# design.net
KiCad netlist of a schematic drawn in Altium Designer
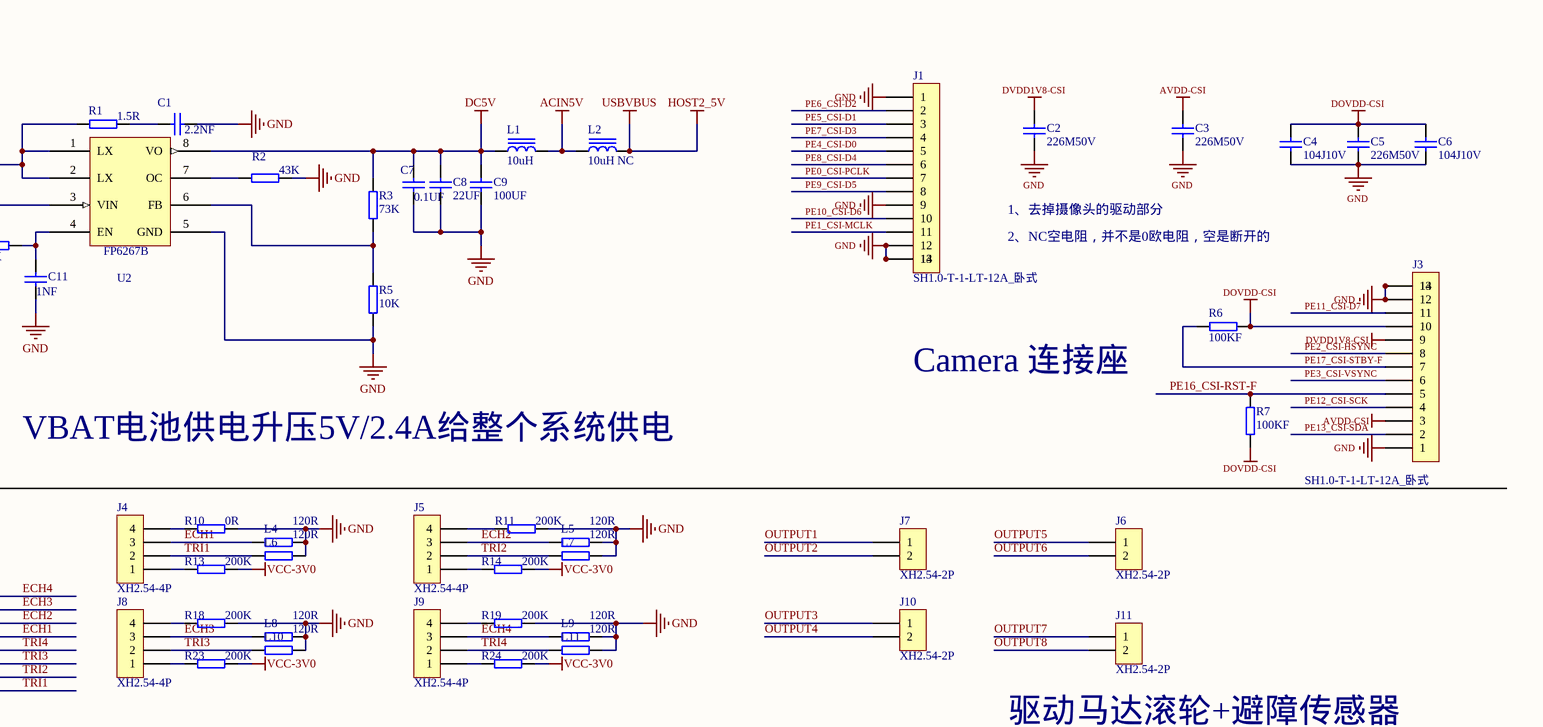
[diagram p0: 宠物机器人&导购机器人.SchDoc, top right]
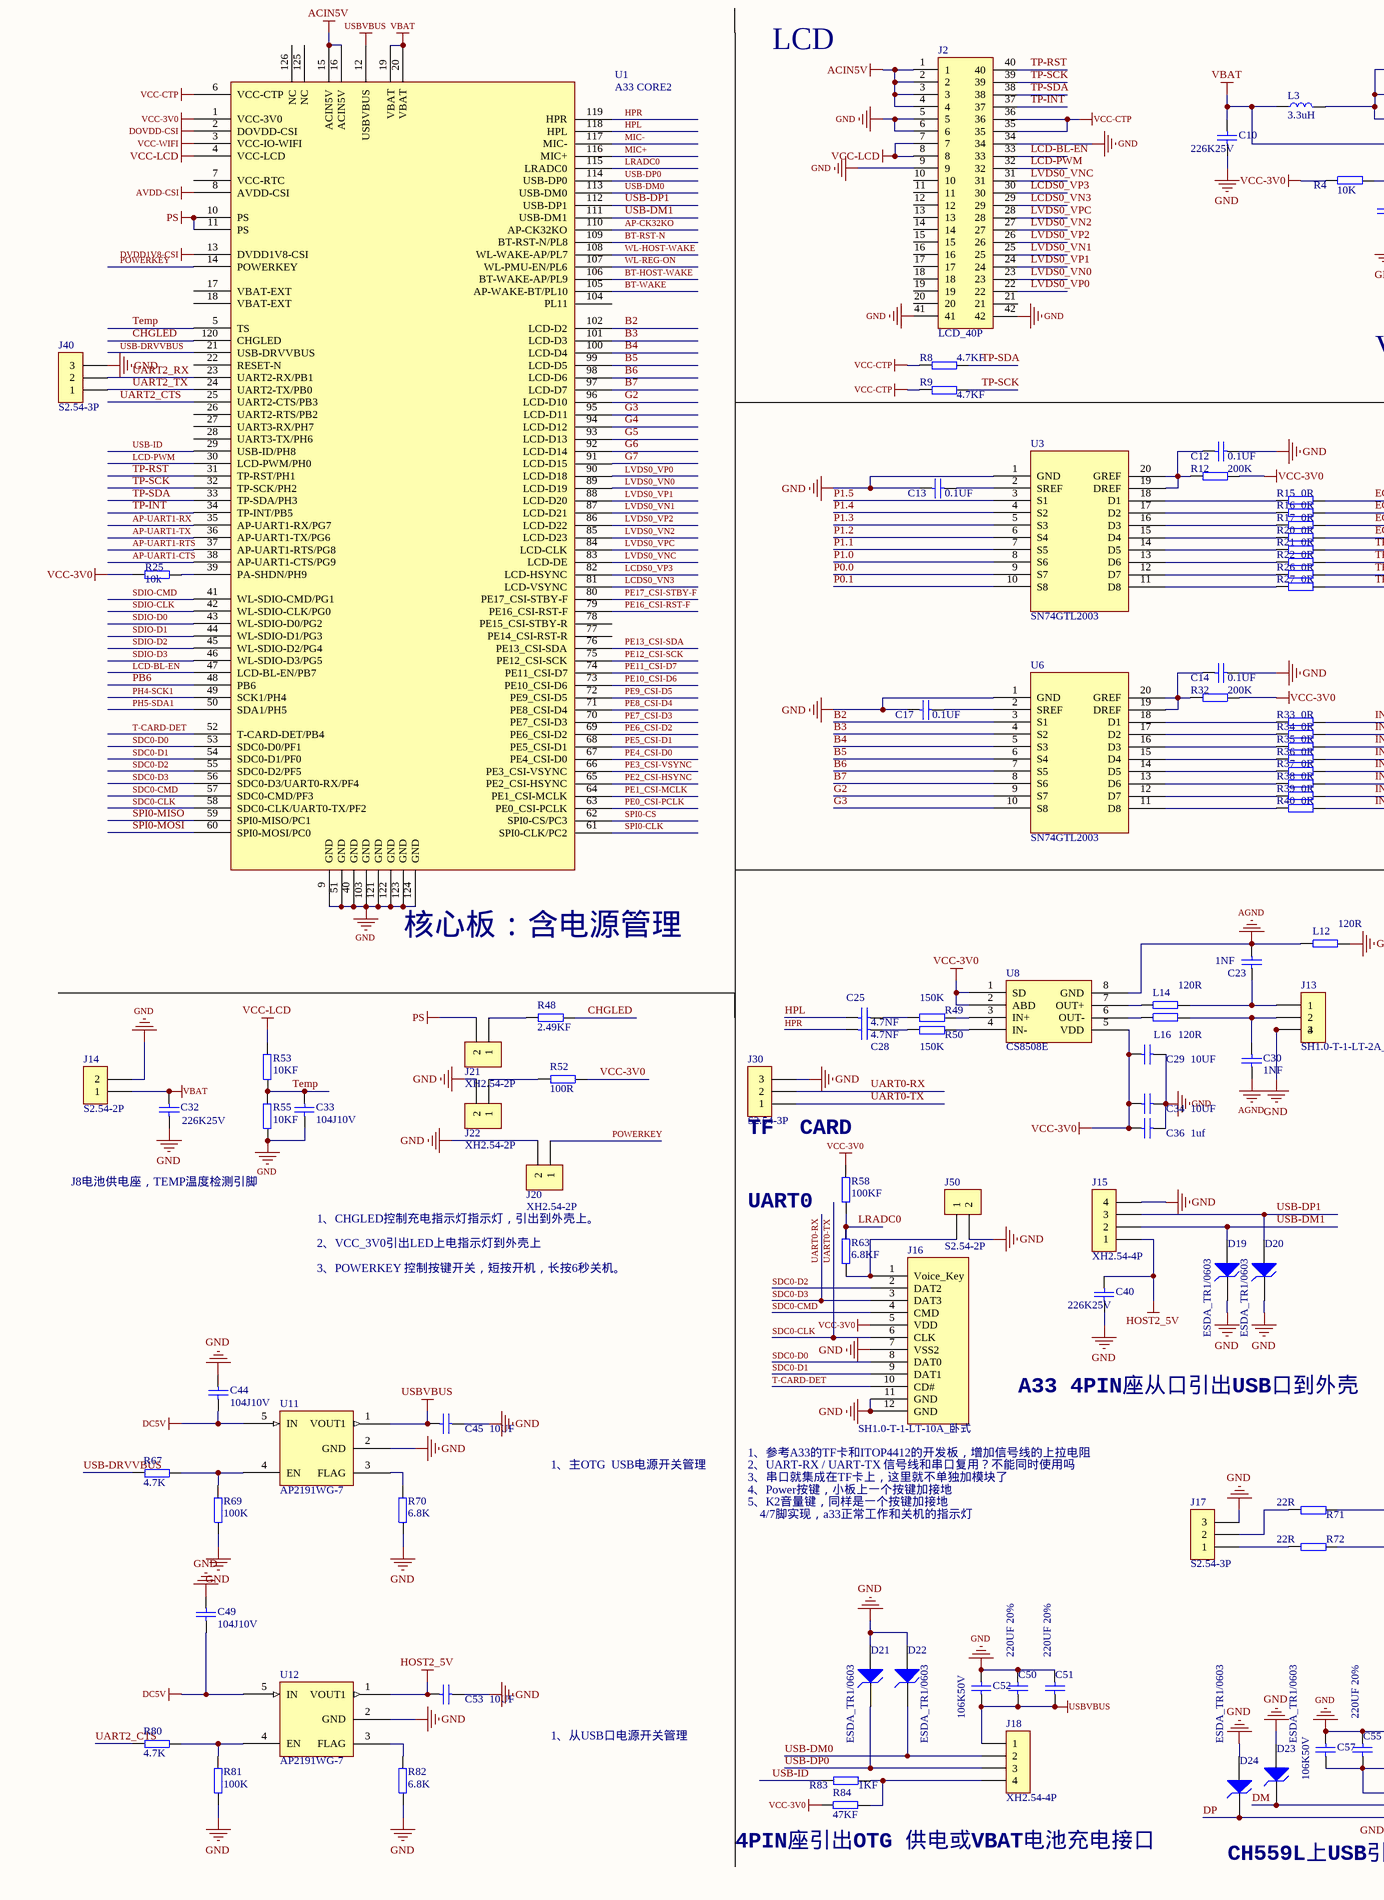
[diagram p1: 宠物机器人&导购机器人.SchDoc, bottom left]
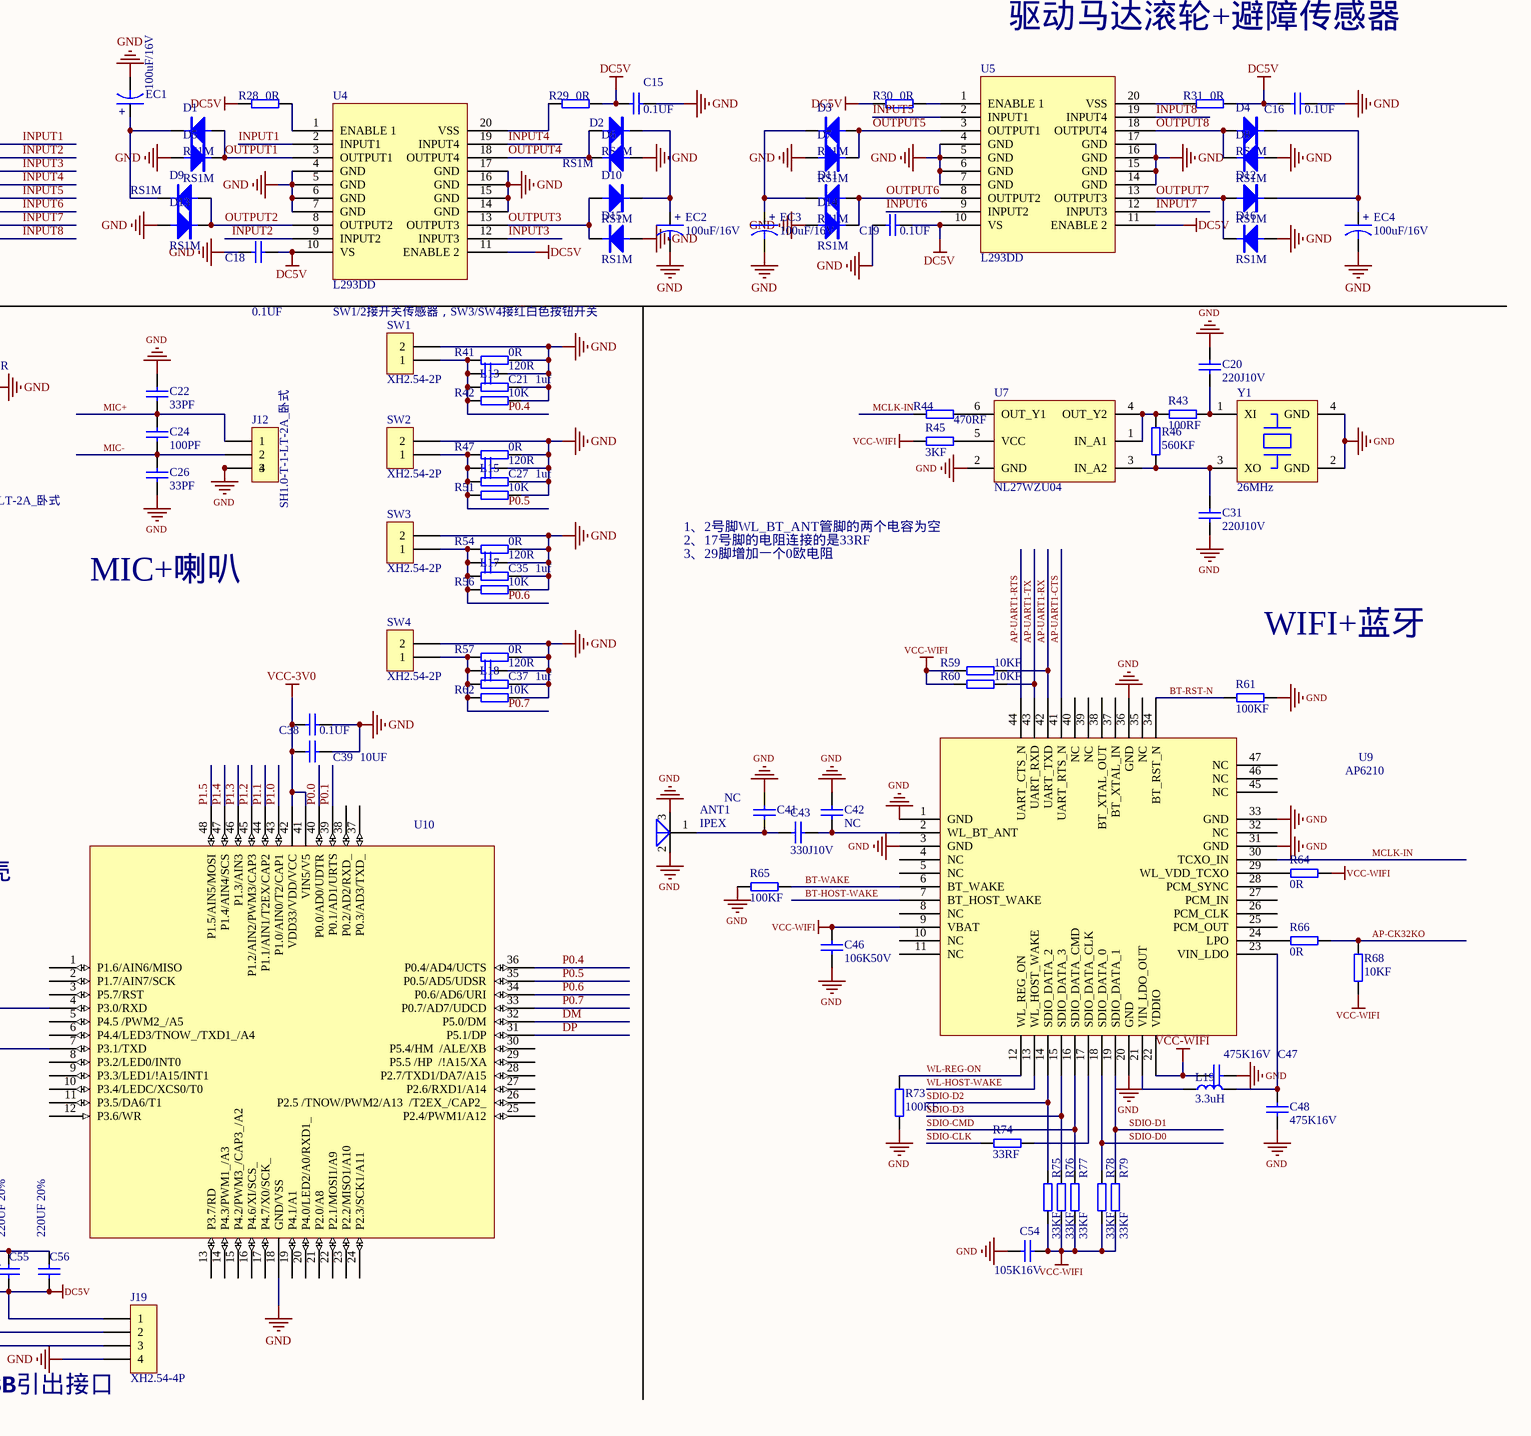
[diagram p2: 宠物机器人&导购机器人.SchDoc, bottom right]

(export (version "E")
  (design (tool "Eeschema 10.0.6"))
  (components
    (comp (ref "ANT1")
      (value "IPEX")
      (footprint "J-IPEX")
      (description "天线接口IPEX")
      (libsource (lib "Connector") (part "J-IPEX"))
    )
    (comp (ref "C1")
      (value "2.2NF")
      (footprint "C0603")
      (description "贴片电容-陶瓷")
      (libsource (lib "Capacitor") (part "C0603X7R-330J25V"))
    )
    (comp (ref "C2")
      (value "226M50V")
      (footprint "C0805")
      (description "贴片电容-陶瓷")
      (libsource (lib "Capacitor") (part "C0805Y5V-226M50V"))
    )
    (comp (ref "C3")
      (value "226M50V")
      (footprint "C0805")
      (description "贴片电容-陶瓷")
      (libsource (lib "Capacitor") (part "C0805Y5V-226M50V"))
    )
    (comp (ref "C4")
      (value "104J10V")
      (footprint "C0402")
      (description "贴片电容-陶瓷")
      (libsource (lib "Capacitor") (part "C0402X7R-104J10V"))
    )
    (comp (ref "C5")
      (value "226M50V")
      (footprint "C0805")
      (description "贴片电容-陶瓷")
      (libsource (lib "Capacitor") (part "C0805Y5V-226M50V"))
    )
    (comp (ref "C6")
      (value "104J10V")
      (footprint "C0402")
      (description "贴片电容-陶瓷")
      (libsource (lib "Capacitor") (part "C0402X7R-104J10V"))
    )
    (comp (ref "C7")
      (value "0.1UF")
      (footprint "C0402")
      (description "贴片电容-陶瓷")
      (libsource (lib "AIWAC-bolsterV01") (part "C0402X7R-101J10V"))
    )
    (comp (ref "C8")
      (value "22UF")
      (footprint "C0603")
      (description "贴片电容-陶瓷")
      (libsource (lib "Capacitor") (part "C0603X7R-330J25V"))
    )
    (comp (ref "C9")
      (value "100UF")
      (footprint "CD3X5.3SMD")
      (description "贴片电容-陶瓷")
      (libsource (lib "Capacitor") (part "C0603X7R-330J25V"))
    )
    (comp (ref "C10")
      (value "226K25V")
      (footprint "C0805")
      (description "贴片电容-陶瓷")
      (libsource (lib "Capacitor") (part "C0805X7R-226K25V"))
    )
    (comp (ref "C11")
      (value "1NF")
      (footprint "C0402")
      (description "贴片电容-陶瓷")
      (libsource (lib "AIWAC-bolsterV01") (part "C0402X7R-101J10V"))
    )
    (comp (ref "C12")
      (value "0.1UF")
      (footprint "C0603")
      (description "贴片电容-陶瓷")
      (libsource (lib "Capacitor") (part "C0603X7R-330J25V"))
    )
    (comp (ref "C13")
      (value "0.1UF")
      (footprint "C0603")
      (description "贴片电容-陶瓷")
      (libsource (lib "Capacitor") (part "C0603X7R-330J25V"))
    )
    (comp (ref "C14")
      (value "0.1UF")
      (footprint "C0603")
      (description "贴片电容-陶瓷")
      (libsource (lib "Capacitor") (part "C0603X7R-330J25V"))
    )
    (comp (ref "C15")
      (value "0.1UF")
      (footprint "C0603")
      (description "贴片电容-陶瓷")
      (libsource (lib "Capacitor") (part "C0603X7R-330J25V"))
    )
    (comp (ref "C16")
      (value "0.1UF")
      (footprint "C0603")
      (description "贴片电容-陶瓷")
      (libsource (lib "Capacitor") (part "C0603X7R-330J25V"))
    )
    (comp (ref "C17")
      (value "0.1UF")
      (footprint "C0603")
      (description "贴片电容-陶瓷")
      (libsource (lib "Capacitor") (part "C0603X7R-330J25V"))
    )
    (comp (ref "C18")
      (value "0.1UF")
      (footprint "C0603")
      (description "贴片电容-陶瓷")
      (libsource (lib "Capacitor") (part "C0603X7R-330J25V"))
    )
    (comp (ref "C19")
      (value "0.1UF")
      (footprint "C0603")
      (description "贴片电容-陶瓷")
      (libsource (lib "Capacitor") (part "C0603X7R-330J25V"))
    )
    (comp (ref "C20")
      (value "220J10V")
      (footprint "C0402")
      (description "贴片电容-陶瓷")
      (libsource (lib "Capacitor") (part "C0402X7R-220J10V"))
    )
    (comp (ref "C21")
      (value "1uf")
      (footprint "C0603")
      (description "贴片电容-陶瓷")
      (libsource (lib "Capacitor") (part "C0603X7R-330J25V"))
    )
    (comp (ref "C22")
      (value "33PF")
      (footprint "C0402")
      (description "贴片电容-陶瓷")
      (libsource (lib "Capacitor") (part "C0402X7R-104J10V"))
    )
    (comp (ref "C23")
      (value "1NF")
      (footprint "C0402")
      (description "贴片电容-陶瓷")
      (libsource (lib "Capacitor") (part "C0402X7R-220J10V"))
    )
    (comp (ref "C24")
      (value "100PF")
      (footprint "C0402")
      (description "贴片电容-陶瓷")
      (libsource (lib "Capacitor") (part "C0402X7R-104J10V"))
    )
    (comp (ref "C25")
      (value "4.7NF")
      (footprint "C0603")
      (description "贴片电容-陶瓷")
      (libsource (lib "Capacitor") (part "C0603X7R-330J25V"))
    )
    (comp (ref "C26")
      (value "33PF")
      (footprint "C0402")
      (description "贴片电容-陶瓷")
      (libsource (lib "Capacitor") (part "C0402X7R-104J10V"))
    )
    (comp (ref "C27")
      (value "1uf")
      (footprint "C0603")
      (description "贴片电容-陶瓷")
      (libsource (lib "Capacitor") (part "C0603X7R-330J25V"))
    )
    (comp (ref "C28")
      (value "4.7NF")
      (footprint "C0603")
      (description "贴片电容-陶瓷")
      (libsource (lib "Capacitor") (part "C0603X7R-330J25V"))
    )
    (comp (ref "C29")
      (value "10UF")
      (footprint "C0603")
      (description "贴片电容-陶瓷")
      (libsource (lib "Capacitor") (part "C0603X7R-330J25V"))
    )
    (comp (ref "C30")
      (value "1NF")
      (footprint "C0402")
      (description "贴片电容-陶瓷")
      (libsource (lib "Capacitor") (part "C0402X7R-220J10V"))
    )
    (comp (ref "C31")
      (value "220J10V")
      (footprint "C0402")
      (description "贴片电容-陶瓷")
      (libsource (lib "Capacitor") (part "C0402X7R-220J10V"))
    )
    (comp (ref "C32")
      (value "226K25V")
      (footprint "C0805")
      (description "贴片电容-陶瓷")
      (libsource (lib "Capacitor") (part "C0805X7R-226K25V"))
    )
    (comp (ref "C33")
      (value "104J10V")
      (footprint "C0402")
      (description "贴片电容-陶瓷")
      (libsource (lib "Capacitor") (part "C0402X7R-104J10V"))
    )
    (comp (ref "C34")
      (value "10UF")
      (footprint "C0603")
      (description "贴片电容-陶瓷")
      (libsource (lib "Capacitor") (part "C0603X7R-330J25V"))
    )
    (comp (ref "C35")
      (value "1uf")
      (footprint "C0603")
      (description "贴片电容-陶瓷")
      (libsource (lib "Capacitor") (part "C0603X7R-330J25V"))
    )
    (comp (ref "C36")
      (value "1uf")
      (footprint "C0603")
      (description "贴片电容-陶瓷")
      (libsource (lib "Capacitor") (part "C0603X7R-330J25V"))
    )
    (comp (ref "C37")
      (value "1uf")
      (footprint "C0603")
      (description "贴片电容-陶瓷")
      (libsource (lib "Capacitor") (part "C0603X7R-330J25V"))
    )
    (comp (ref "C38")
      (value "0.1UF")
      (footprint "C0603")
      (description "贴片电容-陶瓷")
      (libsource (lib "Capacitor") (part "C0603X7R-330J25V"))
    )
    (comp (ref "C39")
      (value "10UF")
      (footprint "C0603")
      (description "贴片电容-陶瓷")
      (libsource (lib "Capacitor") (part "C0603X7R-330J25V"))
    )
    (comp (ref "C40")
      (value "226K25V")
      (footprint "C0805")
      (description "贴片电容-陶瓷")
      (libsource (lib "Capacitor") (part "C0805X7R-226K25V"))
    )
    (comp (ref "C41")
      (value "NC")
      (footprint "C0402")
      (description "贴片电容-陶瓷")
      (libsource (lib "Capacitor") (part "C0402X7R-220J10V"))
    )
    (comp (ref "C42")
      (value "NC")
      (footprint "C0402")
      (description "贴片电容-陶瓷")
      (libsource (lib "Capacitor") (part "C0402X7R-220J10V"))
    )
    (comp (ref "C43")
      (value "330J10V")
      (footprint "C0402")
      (description "贴片电容-陶瓷")
      (libsource (lib "Capacitor") (part "C0402X7R-330J10V"))
    )
    (comp (ref "C44")
      (value "104J10V")
      (footprint "C0402")
      (description "贴片电容-陶瓷")
      (libsource (lib "Capacitor") (part "C0402X7R-104J10V"))
    )
    (comp (ref "C45")
      (value "10UF")
      (footprint "C0603")
      (description "贴片电容-陶瓷")
      (libsource (lib "Capacitor") (part "C0603X7R-330J25V"))
    )
    (comp (ref "C46")
      (value "106K50V")
      (footprint "C0603")
      (description "贴片电容-陶瓷")
      (libsource (lib "Capacitor") (part "C0603X7R-106K50V"))
    )
    (comp (ref "C47")
      (value "475K16V")
      (footprint "C0603")
      (description "贴片电容-陶瓷")
      (libsource (lib "Capacitor") (part "C0603X7R-475K16V"))
    )
    (comp (ref "C48")
      (value "475K16V")
      (footprint "C0603")
      (description "贴片电容-陶瓷")
      (libsource (lib "Capacitor") (part "C0603X7R-475K16V"))
    )
    (comp (ref "C49")
      (value "104J10V")
      (footprint "C0402")
      (description "贴片电容-陶瓷")
      (libsource (lib "Capacitor") (part "C0402X7R-104J10V"))
    )
    (comp (ref "C50")
      (value "220UF 20%")
      (footprint "C1206")
      (description "C 1206钽电容 --220UF 10V 3216 A型 有极性电容 3.2mm X 1.6mm")
      (libsource (lib "Capacitor") (part "C1206-A型 极性电容"))
    )
    (comp (ref "C51")
      (value "220UF 20%")
      (footprint "C1206")
      (description "C 1206钽电容 --220UF 10V 3216 A型 有极性电容 3.2mm X 1.6mm")
      (libsource (lib "Capacitor") (part "C1206-A型 极性电容"))
    )
    (comp (ref "C52")
      (value "106K50V")
      (footprint "C0603")
      (description "贴片电容-陶瓷")
      (libsource (lib "Capacitor") (part "C0603X7R-106K50V"))
    )
    (comp (ref "C53")
      (value "10UF")
      (footprint "C0603")
      (description "贴片电容-陶瓷")
      (libsource (lib "Capacitor") (part "C0603X7R-330J25V"))
    )
    (comp (ref "C54")
      (value "105K16V")
      (footprint "C0603")
      (description "贴片电容-陶瓷")
      (libsource (lib "Capacitor") (part "C0603X7R-105K16V"))
    )
    (comp (ref "C55")
      (value "220UF 20%")
      (footprint "C1206")
      (description "C 1206钽电容 --220UF 10V 3216 A型 有极性电容 3.2mm X 1.6mm")
      (libsource (lib "Capacitor") (part "C1206-A型 极性电容"))
    )
    (comp (ref "C56")
      (value "220UF 20%")
      (footprint "C1206")
      (description "C 1206钽电容 --220UF 10V 3216 A型 有极性电容 3.2mm X 1.6mm")
      (libsource (lib "Capacitor") (part "C1206-A型 极性电容"))
    )
    (comp (ref "C57")
      (value "106K50V")
      (footprint "C0603")
      (description "贴片电容-陶瓷")
      (libsource (lib "Capacitor") (part "C0603X7R-106K50V"))
    )
    (comp (ref "D1")
      (value "RS1M")
      (footprint "D-SMA/DO-214AC")
      (description "贴片二极管-快恢复")
      (libsource (lib "Sheye-Diode") (part "DF-RS1M-1A1000V"))
    )
    (comp (ref "D2")
      (value "RS1M")
      (footprint "D-SMA/DO-214AC")
      (description "贴片二极管-快恢复")
      (libsource (lib "Sheye-Diode") (part "DF-RS1M-1A1000V"))
    )
    (comp (ref "D3")
      (value "RS1M")
      (footprint "D-SMA/DO-214AC")
      (description "贴片二极管-快恢复")
      (libsource (lib "Sheye-Diode") (part "DF-RS1M-1A1000V"))
    )
    (comp (ref "D4")
      (value "RS1M")
      (footprint "D-SMA/DO-214AC")
      (description "贴片二极管-快恢复")
      (libsource (lib "Sheye-Diode") (part "DF-RS1M-1A1000V"))
    )
    (comp (ref "D5")
      (value "RS1M")
      (footprint "D-SMA/DO-214AC")
      (description "贴片二极管-快恢复")
      (libsource (lib "Sheye-Diode") (part "DF-RS1M-1A1000V"))
    )
    (comp (ref "D6")
      (value "RS1M")
      (footprint "D-SMA/DO-214AC")
      (description "贴片二极管-快恢复")
      (libsource (lib "Sheye-Diode") (part "DF-RS1M-1A1000V"))
    )
    (comp (ref "D7")
      (value "RS1M")
      (footprint "D-SMA/DO-214AC")
      (description "贴片二极管-快恢复")
      (libsource (lib "Sheye-Diode") (part "DF-RS1M-1A1000V"))
    )
    (comp (ref "D8")
      (value "RS1M")
      (footprint "D-SMA/DO-214AC")
      (description "贴片二极管-快恢复")
      (libsource (lib "Sheye-Diode") (part "DF-RS1M-1A1000V"))
    )
    (comp (ref "D9")
      (value "RS1M")
      (footprint "D-SMA/DO-214AC")
      (description "贴片二极管-快恢复")
      (libsource (lib "Sheye-Diode") (part "DF-RS1M-1A1000V"))
    )
    (comp (ref "D10")
      (value "RS1M")
      (footprint "D-SMA/DO-214AC")
      (description "贴片二极管-快恢复")
      (libsource (lib "Sheye-Diode") (part "DF-RS1M-1A1000V"))
    )
    (comp (ref "D11")
      (value "RS1M")
      (footprint "D-SMA/DO-214AC")
      (description "贴片二极管-快恢复")
      (libsource (lib "Sheye-Diode") (part "DF-RS1M-1A1000V"))
    )
    (comp (ref "D12")
      (value "RS1M")
      (footprint "D-SMA/DO-214AC")
      (description "贴片二极管-快恢复")
      (libsource (lib "Sheye-Diode") (part "DF-RS1M-1A1000V"))
    )
    (comp (ref "D13")
      (value "RS1M")
      (footprint "D-SMA/DO-214AC")
      (description "贴片二极管-快恢复")
      (libsource (lib "Sheye-Diode") (part "DF-RS1M-1A1000V"))
    )
    (comp (ref "D14")
      (value "RS1M")
      (footprint "D-SMA/DO-214AC")
      (description "贴片二极管-快恢复")
      (libsource (lib "Sheye-Diode") (part "DF-RS1M-1A1000V"))
    )
    (comp (ref "D15")
      (value "RS1M")
      (footprint "D-SMA/DO-214AC")
      (description "贴片二极管-快恢复")
      (libsource (lib "Sheye-Diode") (part "DF-RS1M-1A1000V"))
    )
    (comp (ref "D16")
      (value "RS1M")
      (footprint "D-SMA/DO-214AC")
      (description "贴片二极管-快恢复")
      (libsource (lib "Sheye-Diode") (part "DF-RS1M-1A1000V"))
    )
    (comp (ref "D19")
      (value "ESDA_TR1/0603")
      (footprint "HS_0603D")
      (description "Zener Diode")
      (fields (field (name "PUBLISHER") "*"))
      (libsource (lib "1_1") (part "D Zener"))
    )
    (comp (ref "D20")
      (value "ESDA_TR1/0603")
      (footprint "HS_0603D")
      (description "Zener Diode")
      (fields (field (name "PUBLISHER") "*"))
      (libsource (lib "1_1") (part "D Zener"))
    )
    (comp (ref "D21")
      (value "ESDA_TR1/0603")
      (footprint "HS_0603D")
      (description "Zener Diode")
      (fields (field (name "PUBLISHER") "*"))
      (libsource (lib "1_1") (part "D Zener"))
    )
    (comp (ref "D22")
      (value "ESDA_TR1/0603")
      (footprint "HS_0603D")
      (description "Zener Diode")
      (fields (field (name "PUBLISHER") "*"))
      (libsource (lib "1_1") (part "D Zener"))
    )
    (comp (ref "D23")
      (value "ESDA_TR1/0603")
      (footprint "HS_0603D")
      (description "Zener Diode")
      (fields (field (name "PUBLISHER") "*"))
      (libsource (lib "1_1") (part "D Zener"))
    )
    (comp (ref "D24")
      (value "ESDA_TR1/0603")
      (footprint "HS_0603D")
      (description "Zener Diode")
      (fields (field (name "PUBLISHER") "*"))
      (libsource (lib "1_1") (part "D Zener"))
    )
    (comp (ref "EC1")
      (value "100uF/16V")
      (footprint "CD6.3x8SMD")
      (description "贴片铝电解电容")
      (libsource (lib "Sheye-Capacitor") (part "CES-100uF/16V"))
    )
    (comp (ref "EC2")
      (value "100uF/16V")
      (footprint "CD6.3x8SMD")
      (description "贴片铝电解电容")
      (libsource (lib "Sheye-Capacitor") (part "CES-100uF/16V"))
    )
    (comp (ref "EC3")
      (value "100uF/16V")
      (footprint "CD6.3x8SMD")
      (description "贴片铝电解电容")
      (libsource (lib "Sheye-Capacitor") (part "CES-100uF/16V"))
    )
    (comp (ref "EC4")
      (value "100uF/16V")
      (footprint "CD6.3x8SMD")
      (description "贴片铝电解电容")
      (libsource (lib "Sheye-Capacitor") (part "CES-100uF/16V"))
    )
    (comp (ref "J1")
      (value "SH1.0-T-1-LT-12A_卧式")
      (footprint "J-SH1.0-T-1-LT-12A_立式")
      (libsource (lib "") (part "SH1.0-T-1-LT-12A_卧式_1"))
    )
    (comp (ref "J2") (value "LCD_40P") (footprint "LCD P40") (libsource (lib "Connector") (part "LCD_40P")))
    (comp (ref "J3")
      (value "SH1.0-T-1-LT-12A_卧式")
      (footprint "J-SH1.0-T-1-LT-12A_立式")
      (libsource (lib "Connector") (part "SH1.0-T-1-LT-12A_卧式"))
    )
    (comp (ref "J4")
      (value "XH2.54-4P")
      (footprint "XH2.54-4P")
      (description "接插件-2.54")
      (libsource (lib "AIWAC-bolsterV01") (part "J-XH2.54-4P"))
    )
    (comp (ref "J5")
      (value "XH2.54-4P")
      (footprint "XH2.54-4P")
      (description "接插件-2.54")
      (libsource (lib "AIWAC-bolsterV01") (part "J-XH2.54-4P"))
    )
    (comp (ref "J6")
      (value "XH2.54-2P")
      (footprint "XH2.54-2P")
      (description "接插件-2.54")
      (libsource (lib "AIWAC-bolsterV01") (part "J-XH2.54-2P"))
    )
    (comp (ref "J7")
      (value "XH2.54-2P")
      (footprint "XH2.54-2P")
      (description "接插件-2.54")
      (libsource (lib "AIWAC-bolsterV01") (part "J-XH2.54-2P"))
    )
    (comp (ref "J8")
      (value "XH2.54-4P")
      (footprint "XH2.54-4P")
      (description "接插件-2.54")
      (libsource (lib "AIWAC-bolsterV01") (part "J-XH2.54-4P"))
    )
    (comp (ref "J9")
      (value "XH2.54-4P")
      (footprint "XH2.54-4P")
      (description "接插件-2.54")
      (libsource (lib "AIWAC-bolsterV01") (part "J-XH2.54-4P"))
    )
    (comp (ref "J10")
      (value "XH2.54-2P")
      (footprint "XH2.54-2P")
      (description "接插件-2.54")
      (libsource (lib "AIWAC-bolsterV01") (part "J-XH2.54-2P"))
    )
    (comp (ref "J11")
      (value "XH2.54-2P")
      (footprint "XH2.54-2P")
      (description "接插件-2.54")
      (libsource (lib "AIWAC-bolsterV01") (part "J-XH2.54-2P"))
    )
    (comp (ref "J12")
      (value "SH1.0-T-1-LT-2A_卧式")
      (footprint "J-SH2.0-T-1-LT-2A_立式")
      (libsource (lib "Connector") (part "SH1.0-T-1-LT-2A_卧式"))
    )
    (comp (ref "J13")
      (value "SH1.0-T-1-LT-2A_卧式")
      (footprint "J-SH2.0-T-1-LT-2A_立式")
      (libsource (lib "Connector") (part "SH1.0-T-1-LT-2A_卧式"))
    )
    (comp (ref "J14")
      (value "S2.54-2P")
      (footprint "S2.54-2P")
      (description "单排排针-直针")
      (libsource (lib "Sheye-Connector") (part "J-S2.54-2P"))
    )
    (comp (ref "J15")
      (value "XH2.54-4P")
      (footprint "XH2.54-4P")
      (description "接插件-2.54")
      (libsource (lib "Sheye-Connector") (part "J-XH2.54-4P"))
    )
    (comp (ref "J16")
      (value "SH1.0-T-1-LT-10A_卧式")
      (footprint "J-SH1.0-T-1-LT-10A_立式")
      (libsource (lib "Connector") (part "SH1.0-T-1-LT-10A_卧式"))
    )
    (comp (ref "J17")
      (value "S2.54-3P")
      (footprint "S2.54-3P")
      (description "单排排针-直针")
      (libsource (lib "Sheye-Connector") (part "J-S2.54-3P"))
    )
    (comp (ref "J18")
      (value "XH2.54-4P")
      (footprint "XH2.54-4P")
      (description "接插件-2.54")
      (libsource (lib "") (part "J-XH2.54-4P_1"))
    )
    (comp (ref "J19")
      (value "XH2.54-4P")
      (footprint "XH2.54-4P")
      (description "接插件-2.54")
      (libsource (lib "") (part "J-XH2.54-4P_1"))
    )
    (comp (ref "J20")
      (value "XH2.54-2P")
      (footprint "XH2.54-2P")
      (description "接插件-2.54")
      (libsource (lib "") (part "J-XH2.54-2P_1"))
    )
    (comp (ref "J21")
      (value "XH2.54-2P")
      (footprint "XH2.54-2P")
      (description "接插件-2.54")
      (libsource (lib "") (part "J-XH2.54-2P_1"))
    )
    (comp (ref "J22")
      (value "XH2.54-2P")
      (footprint "XH2.54-2P")
      (description "接插件-2.54")
      (libsource (lib "") (part "J-XH2.54-2P_1"))
    )
    (comp (ref "J30")
      (value "S2.54-3P")
      (footprint "S2.54-3P")
      (description "单排排针-直针")
      (libsource (lib "PCB_Project") (part "J-S2.54-3P"))
    )
    (comp (ref "J40")
      (value "S2.54-3P")
      (footprint "S2.54-3P")
      (description "单排排针-直针")
      (libsource (lib "PCB_Project") (part "J-S2.54-3P"))
    )
    (comp (ref "J50")
      (value "S2.54-2P")
      (footprint "S2.54-2P")
      (description "单排排针-直针")
      (libsource (lib "PCB_Project") (part "J-S2.54-2P"))
    )
    (comp (ref "L1")
      (value "10uH")
      (footprint "C0603")
      (description "插件电感-工形")
      (libsource (lib "AIWAC-bolsterV01") (part "LI-0608-10uH1A"))
    )
    (comp (ref "L2")
      (value "10uH NC")
      (footprint "C0603")
      (description "插件电感-工形")
      (libsource (lib "AIWAC-bolsterV01") (part "LI-0608-10uH1A"))
    )
    (comp (ref "L3")
      (value "3.3uH")
      (footprint "LSMD3521")
      (description "贴片电感-屏蔽")
      (libsource (lib "AIWAC-bolsterV01") (part "3.3uH"))
    )
    (comp (ref "L4")
      (value "120R")
      (footprint "R0603")
      (description "贴片电阻-通用")
      (libsource (lib "Resistor") (part "R0603-47KF"))
    )
    (comp (ref "L5")
      (value "120R")
      (footprint "R0603")
      (description "贴片电阻-通用")
      (libsource (lib "Resistor") (part "R0603-47KF"))
    )
    (comp (ref "L6")
      (value "120R")
      (footprint "R0603")
      (description "贴片电阻-通用")
      (libsource (lib "Resistor") (part "R0603-47KF"))
    )
    (comp (ref "L7")
      (value "120R")
      (footprint "R0603")
      (description "贴片电阻-通用")
      (libsource (lib "Resistor") (part "R0603-47KF"))
    )
    (comp (ref "L8")
      (value "120R")
      (footprint "R0603")
      (description "贴片电阻-通用")
      (libsource (lib "Resistor") (part "R0603-47KF"))
    )
    (comp (ref "L9")
      (value "120R")
      (footprint "R0603")
      (description "贴片电阻-通用")
      (libsource (lib "Resistor") (part "R0603-47KF"))
    )
    (comp (ref "L10")
      (value "120R")
      (footprint "R0603")
      (description "贴片电阻-通用")
      (libsource (lib "Resistor") (part "R0603-47KF"))
    )
    (comp (ref "L11")
      (value "120R")
      (footprint "R0603")
      (description "贴片电阻-通用")
      (libsource (lib "Resistor") (part "R0603-47KF"))
    )
    (comp (ref "L12")
      (value "120R")
      (footprint "R0603")
      (description "贴片电阻-通用")
      (libsource (lib "Resistor") (part "R0603-47KF"))
    )
    (comp (ref "L13")
      (value "120R")
      (footprint "R0603")
      (description "贴片电阻-通用")
      (libsource (lib "Resistor") (part "R0603-47KF"))
    )
    (comp (ref "L14")
      (value "120R")
      (footprint "R0603")
      (description "贴片电阻-通用")
      (libsource (lib "Resistor") (part "R0603-47KF"))
    )
    (comp (ref "L15")
      (value "120R")
      (footprint "R0603")
      (description "贴片电阻-通用")
      (libsource (lib "Resistor") (part "R0603-47KF"))
    )
    (comp (ref "L16")
      (value "120R")
      (footprint "R0603")
      (description "贴片电阻-通用")
      (libsource (lib "Resistor") (part "R0603-47KF"))
    )
    (comp (ref "L17")
      (value "120R")
      (footprint "R0603")
      (description "贴片电阻-通用")
      (libsource (lib "Resistor") (part "R0603-47KF"))
    )
    (comp (ref "L18")
      (value "120R")
      (footprint "R0603")
      (description "贴片电阻-通用")
      (libsource (lib "Resistor") (part "R0603-47KF"))
    )
    (comp (ref "L19")
      (value "3.3uH")
      (footprint "L0805")
      (description "贴片电感-层叠")
      (libsource (lib "magnetic") (part "L-0805-3.3uH"))
    )
    (comp (ref "R1")
      (value "1.5R")
      (footprint "R0603")
      (description "贴片电阻-通用")
      (libsource (lib "Resistor") (part "R0603-2KF"))
    )
    (comp (ref "R2")
      (value "43K")
      (footprint "R0603")
      (description "贴片电阻-通用")
      (libsource (lib "Resistor") (part "R0603-2KF"))
    )
    (comp (ref "R3")
      (value "73K")
      (footprint "R0603")
      (description "贴片电阻-通用")
      (libsource (lib "Resistor") (part "R0603-2KF"))
    )
    (comp (ref "R4")
      (value "10K")
      (footprint "R0603")
      (description "贴片电阻-通用")
      (libsource (lib "Resistor") (part "R0603-2KF"))
    )
    (comp (ref "R5")
      (value "10K")
      (footprint "R0603")
      (description "贴片电阻-通用")
      (libsource (lib "Resistor") (part "R0603-2KF"))
    )
    (comp (ref "R6")
      (value "100KF")
      (footprint "R0603")
      (description "贴片电阻-通用")
      (libsource (lib "Resistor") (part "R0603-100KF"))
    )
    (comp (ref "R7")
      (value "100KF")
      (footprint "R0603")
      (description "贴片电阻-通用")
      (libsource (lib "Resistor") (part "R0603-100KF"))
    )
    (comp (ref "R8")
      (value "4.7KF")
      (footprint "R0402")
      (description "贴片电阻-通用")
      (libsource (lib "Resistor") (part "R0402-4.7KF"))
    )
    (comp (ref "R9")
      (value "4.7KF")
      (footprint "R0402")
      (description "贴片电阻-通用")
      (libsource (lib "Resistor") (part "R0402-4.7KF"))
    )
    (comp (ref "R10")
      (value "0R")
      (footprint "R0402")
      (description "贴片电阻-通用")
      (libsource (lib "Resistor") (part "R0402-4.7KF"))
    )
    (comp (ref "R11")
      (value "200K")
      (footprint "R0402")
      (description "贴片电阻-通用")
      (libsource (lib "Resistor") (part "R0402-4.7KF"))
    )
    (comp (ref "R12")
      (value "200K")
      (footprint "R0402")
      (description "贴片电阻-通用")
      (libsource (lib "Resistor") (part "R0402-4.7KF"))
    )
    (comp (ref "R13")
      (value "200K")
      (footprint "R0402")
      (description "贴片电阻-通用")
      (libsource (lib "Resistor") (part "R0402-4.7KF"))
    )
    (comp (ref "R14")
      (value "200K")
      (footprint "R0402")
      (description "贴片电阻-通用")
      (libsource (lib "Resistor") (part "R0402-4.7KF"))
    )
    (comp (ref "R15")
      (value "0R")
      (footprint "R0603")
      (description "贴片电阻-通用")
      (libsource (lib "Resistor") (part "R0603-2KF"))
    )
    (comp (ref "R16")
      (value "0R")
      (footprint "R0603")
      (description "贴片电阻-通用")
      (libsource (lib "Resistor") (part "R0603-2KF"))
    )
    (comp (ref "R17")
      (value "0R")
      (footprint "R0603")
      (description "贴片电阻-通用")
      (libsource (lib "Resistor") (part "R0603-2KF"))
    )
    (comp (ref "R18")
      (value "200K")
      (footprint "R0402")
      (description "贴片电阻-通用")
      (libsource (lib "Resistor") (part "R0402-4.7KF"))
    )
    (comp (ref "R19")
      (value "200K")
      (footprint "R0402")
      (description "贴片电阻-通用")
      (libsource (lib "Resistor") (part "R0402-4.7KF"))
    )
    (comp (ref "R20")
      (value "0R")
      (footprint "R0603")
      (description "贴片电阻-通用")
      (libsource (lib "Resistor") (part "R0603-2KF"))
    )
    (comp (ref "R21")
      (value "0R")
      (footprint "R0603")
      (description "贴片电阻-通用")
      (libsource (lib "Resistor") (part "R0603-2KF"))
    )
    (comp (ref "R22")
      (value "0R")
      (footprint "R0603")
      (description "贴片电阻-通用")
      (libsource (lib "Resistor") (part "R0603-2KF"))
    )
    (comp (ref "R23")
      (value "200K")
      (footprint "R0402")
      (description "贴片电阻-通用")
      (libsource (lib "Resistor") (part "R0402-4.7KF"))
    )
    (comp (ref "R24")
      (value "200K")
      (footprint "R0402")
      (description "贴片电阻-通用")
      (libsource (lib "Resistor") (part "R0402-4.7KF"))
    )
    (comp (ref "R25")
      (value "10k")
      (footprint "R0603")
      (description "贴片电阻-通用")
      (libsource (lib "Resistor") (part "R0603-10KF"))
    )
    (comp (ref "R26")
      (value "0R")
      (footprint "R0603")
      (description "贴片电阻-通用")
      (libsource (lib "Resistor") (part "R0603-2KF"))
    )
    (comp (ref "R27")
      (value "0R")
      (footprint "R0603")
      (description "贴片电阻-通用")
      (libsource (lib "Resistor") (part "R0603-2KF"))
    )
    (comp (ref "R28")
      (value "0R")
      (footprint "R0603")
      (description "贴片电阻-通用")
      (libsource (lib "Resistor") (part "R0603-2KF"))
    )
    (comp (ref "R29")
      (value "0R")
      (footprint "R0603")
      (description "贴片电阻-通用")
      (libsource (lib "Resistor") (part "R0603-2KF"))
    )
    (comp (ref "R30")
      (value "0R")
      (footprint "R0603")
      (description "贴片电阻-通用")
      (libsource (lib "Resistor") (part "R0603-2KF"))
    )
    (comp (ref "R31")
      (value "0R")
      (footprint "R0603")
      (description "贴片电阻-通用")
      (libsource (lib "Resistor") (part "R0603-2KF"))
    )
    (comp (ref "R32")
      (value "200K")
      (footprint "R0402")
      (description "贴片电阻-通用")
      (libsource (lib "Resistor") (part "R0402-4.7KF"))
    )
    (comp (ref "R33")
      (value "0R")
      (footprint "R0603")
      (description "贴片电阻-通用")
      (libsource (lib "Resistor") (part "R0603-2KF"))
    )
    (comp (ref "R34")
      (value "0R")
      (footprint "R0603")
      (description "贴片电阻-通用")
      (libsource (lib "Resistor") (part "R0603-2KF"))
    )
    (comp (ref "R35")
      (value "0R")
      (footprint "R0603")
      (description "贴片电阻-通用")
      (libsource (lib "Resistor") (part "R0603-2KF"))
    )
    (comp (ref "R36")
      (value "0R")
      (footprint "R0603")
      (description "贴片电阻-通用")
      (libsource (lib "Resistor") (part "R0603-2KF"))
    )
    (comp (ref "R37")
      (value "0R")
      (footprint "R0603")
      (description "贴片电阻-通用")
      (libsource (lib "Resistor") (part "R0603-2KF"))
    )
    (comp (ref "R38")
      (value "0R")
      (footprint "R0603")
      (description "贴片电阻-通用")
      (libsource (lib "Resistor") (part "R0603-2KF"))
    )
    (comp (ref "R39")
      (value "0R")
      (footprint "R0603")
      (description "贴片电阻-通用")
      (libsource (lib "Resistor") (part "R0603-2KF"))
    )
    (comp (ref "R40")
      (value "0R")
      (footprint "R0603")
      (description "贴片电阻-通用")
      (libsource (lib "Resistor") (part "R0603-2KF"))
    )
    (comp (ref "R41")
      (value "0R")
      (footprint "R0603")
      (description "贴片电阻-通用")
      (libsource (lib "Resistor") (part "R0603-10KF"))
    )
    (comp (ref "R42")
      (value "10K")
      (footprint "R0603")
      (description "贴片电阻-通用")
      (libsource (lib "Resistor") (part "R0603-10KF"))
    )
    (comp (ref "R43")
      (value "100RF")
      (footprint "R0603")
      (description "贴片电阻-通用")
      (libsource (lib "Resistor") (part "R0603-100RF"))
    )
    (comp (ref "R44")
      (value "470RF")
      (footprint "R0603")
      (description "贴片电阻-通用")
      (libsource (lib "Resistor") (part "R0603-470RF"))
    )
    (comp (ref "R45")
      (value "3KF")
      (footprint "R0603")
      (description "贴片电阻-通用")
      (libsource (lib "Resistor") (part "R0603-3KF"))
    )
    (comp (ref "R46")
      (value "560KF")
      (footprint "R0603")
      (description "贴片电阻-通用")
      (libsource (lib "Resistor") (part "R0603-560KF"))
    )
    (comp (ref "R47")
      (value "0R")
      (footprint "R0603")
      (description "贴片电阻-通用")
      (libsource (lib "Resistor") (part "R0603-10KF"))
    )
    (comp (ref "R48")
      (value "2.49KF")
      (footprint "R0603")
      (description "贴片电阻-通用")
      (libsource (lib "Resistor") (part "R0603-3KF"))
    )
    (comp (ref "R49")
      (value "150K")
      (footprint "R0603")
      (description "贴片电阻-通用")
      (libsource (lib "Resistor") (part "R0603-10KF"))
    )
    (comp (ref "R50")
      (value "150K")
      (footprint "R0603")
      (description "贴片电阻-通用")
      (libsource (lib "Resistor") (part "R0603-10KF"))
    )
    (comp (ref "R51")
      (value "10K")
      (footprint "R0603")
      (description "贴片电阻-通用")
      (libsource (lib "Resistor") (part "R0603-10KF"))
    )
    (comp (ref "R52")
      (value "100R")
      (footprint "R0603")
      (description "贴片电阻-通用")
      (libsource (lib "Resistor") (part "R0603-2KF"))
    )
    (comp (ref "R53")
      (value "10KF")
      (footprint "R0603")
      (description "贴片电阻-通用")
      (libsource (lib "Resistor") (part "R0603-10KF"))
    )
    (comp (ref "R54")
      (value "0R")
      (footprint "R0603")
      (description "贴片电阻-通用")
      (libsource (lib "Resistor") (part "R0603-10KF"))
    )
    (comp (ref "R55")
      (value "10KF")
      (footprint "R0603")
      (description "贴片电阻-通用")
      (libsource (lib "Resistor") (part "R0603-10KF"))
    )
    (comp (ref "R56")
      (value "10K")
      (footprint "R0603")
      (description "贴片电阻-通用")
      (libsource (lib "Resistor") (part "R0603-10KF"))
    )
    (comp (ref "R57")
      (value "0R")
      (footprint "R0603")
      (description "贴片电阻-通用")
      (libsource (lib "Resistor") (part "R0603-10KF"))
    )
    (comp (ref "R58")
      (value "100KF")
      (footprint "R0603")
      (description "贴片电阻-通用")
      (libsource (lib "Resistor") (part "R0603-100KF"))
    )
    (comp (ref "R59")
      (value "10KF")
      (footprint "R0603")
      (description "贴片电阻-通用")
      (libsource (lib "Resistor") (part "R0603-10KF"))
    )
    (comp (ref "R60")
      (value "10KF")
      (footprint "R0603")
      (description "贴片电阻-通用")
      (libsource (lib "Resistor") (part "R0603-10KF"))
    )
    (comp (ref "R61")
      (value "100KF")
      (footprint "R0603")
      (description "贴片电阻-通用")
      (libsource (lib "Resistor") (part "R0603-100KF"))
    )
    (comp (ref "R62")
      (value "10K")
      (footprint "R0603")
      (description "贴片电阻-通用")
      (libsource (lib "Resistor") (part "R0603-10KF"))
    )
    (comp (ref "R63")
      (value "6.8KF")
      (footprint "R0603")
      (description "贴片电阻-通用")
      (libsource (lib "Resistor") (part "R0603-6.8KF"))
    )
    (comp (ref "R64")
      (value "0R")
      (footprint "R0603")
      (description "贴片电阻-通用")
      (libsource (lib "Resistor") (part "R0603-0R"))
    )
    (comp (ref "R65")
      (value "100KF")
      (footprint "R0603")
      (description "贴片电阻-通用")
      (libsource (lib "Resistor") (part "R0603-100KF"))
    )
    (comp (ref "R66")
      (value "0R")
      (footprint "R0603")
      (description "贴片电阻-通用")
      (libsource (lib "Resistor") (part "R0603-0R"))
    )
    (comp (ref "R67")
      (value "4.7K")
      (footprint "R0603")
      (description "贴片电阻-通用")
      (libsource (lib "Resistor") (part "R0603-2KF"))
    )
    (comp (ref "R68")
      (value "10KF")
      (footprint "R0603")
      (description "贴片电阻-通用")
      (libsource (lib "Resistor") (part "R0603-10KF"))
    )
    (comp (ref "R69")
      (value "100K")
      (footprint "R0603")
      (description "贴片电阻-通用")
      (libsource (lib "Resistor") (part "R0603-10KF"))
    )
    (comp (ref "R70")
      (value "6.8K")
      (footprint "R0603")
      (description "贴片电阻-通用")
      (libsource (lib "Resistor") (part "R0603-10KF"))
    )
    (comp (ref "R71")
      (value "22R")
      (footprint "R0603")
      (description "贴片电阻-通用")
      (libsource (lib "Resistor") (part "R0603-10KF"))
    )
    (comp (ref "R72")
      (value "22R")
      (footprint "R0603")
      (description "贴片电阻-通用")
      (libsource (lib "Resistor") (part "R0603-10KF"))
    )
    (comp (ref "R73")
      (value "100KF")
      (footprint "R0603")
      (description "贴片电阻-通用")
      (libsource (lib "Resistor") (part "R0603-100KF"))
    )
    (comp (ref "R74")
      (value "33RF")
      (footprint "R0603")
      (description "贴片电阻-通用")
      (libsource (lib "Resistor") (part "R0603-33RF"))
    )
    (comp (ref "R75")
      (value "33KF")
      (footprint "R0603")
      (description "贴片电阻-通用")
      (libsource (lib "Resistor") (part "R0603-33KF"))
    )
    (comp (ref "R76")
      (value "33KF")
      (footprint "R0603")
      (description "贴片电阻-通用")
      (libsource (lib "Resistor") (part "R0603-33KF"))
    )
    (comp (ref "R77")
      (value "33KF")
      (footprint "R0603")
      (description "贴片电阻-通用")
      (libsource (lib "Resistor") (part "R0603-33KF"))
    )
    (comp (ref "R78")
      (value "33KF")
      (footprint "R0603")
      (description "贴片电阻-通用")
      (libsource (lib "Resistor") (part "R0603-33KF"))
    )
    (comp (ref "R79")
      (value "33KF")
      (footprint "R0603")
      (description "贴片电阻-通用")
      (libsource (lib "Resistor") (part "R0603-33KF"))
    )
    (comp (ref "R80")
      (value "4.7K")
      (footprint "R0603")
      (description "贴片电阻-通用")
      (libsource (lib "Resistor") (part "R0603-2KF"))
    )
    (comp (ref "R81")
      (value "100K")
      (footprint "R0603")
      (description "贴片电阻-通用")
      (libsource (lib "Resistor") (part "R0603-10KF"))
    )
    (comp (ref "R82")
      (value "6.8K")
      (footprint "R0603")
      (description "贴片电阻-通用")
      (libsource (lib "Resistor") (part "R0603-10KF"))
    )
    (comp (ref "R83")
      (value "1KF")
      (footprint "R0603")
      (description "贴片电阻-通用")
      (libsource (lib "Resistor") (part "R0603-1KF"))
    )
    (comp (ref "R84")
      (value "47KF")
      (footprint "R0603")
      (description "贴片电阻-通用")
      (libsource (lib "Resistor") (part "R0603-47KF"))
    )
    (comp (ref "SW1")
      (value "XH2.54-2P")
      (footprint "XH2.54-2P")
      (description "接插件-2.54")
      (libsource (lib "Sheye-Connector") (part "J-XH2.54-2P"))
    )
    (comp (ref "SW2")
      (value "XH2.54-2P")
      (footprint "XH2.54-2P")
      (description "接插件-2.54")
      (libsource (lib "Sheye-Connector") (part "J-XH2.54-2P"))
    )
    (comp (ref "SW3")
      (value "XH2.54-2P")
      (footprint "XH2.54-2P")
      (description "接插件-2.54")
      (libsource (lib "Sheye-Connector") (part "J-XH2.54-2P"))
    )
    (comp (ref "SW4")
      (value "XH2.54-2P")
      (footprint "XH2.54-2P")
      (description "接插件-2.54")
      (libsource (lib "Sheye-Connector") (part "J-XH2.54-2P"))
    )
    (comp (ref "U1")
      (value "A33 CORE2")
      (footprint "aiwac_LCD:A33-CORE2")
      (libsource (lib "Module") (part "A33 CORE2"))
    )
    (comp (ref "U2")
      (value "FP6267B")
      (footprint "U-SOP-8N-1")
      (libsource (lib "AIWAC-bolsterV01") (part "FP6267B"))
    )
    (comp (ref "U3")
      (value "SN74GTL2003")
      (footprint "U-TSSOP20 - duplicate")
      (libsource (lib "AIWAC-bolsterV01") (part "SN74GTL2003"))
    )
    (comp (ref "U4") (value "L293DD") (footprint "S020") (libsource (lib "AIWAC-bolsterV01") (part "L293DD")))
    (comp (ref "U5") (value "L293DD") (footprint "S020") (libsource (lib "AIWAC-bolsterV01") (part "L293DD")))
    (comp (ref "U6")
      (value "SN74GTL2003")
      (footprint "U-TSSOP20 - duplicate")
      (libsource (lib "AIWAC-bolsterV01") (part "SN74GTL2003"))
    )
    (comp (ref "U7") (value "NL27WZU04") (footprint "U-TSOP-6") (libsource (lib "IC") (part "NL27WZU04")))
    (comp (ref "U8") (value "CS8508E") (footprint "SO-8") (libsource (lib "PCB_Project_1") (part "CS8508E")))
    (comp (ref "U9")
      (value "AP6210")
      (footprint "AIWAC-bolsterV01:AP6210")
      (libsource (lib "IC") (part "AP6210"))
    )
    (comp (ref "U10")
      (value "CH559L")
      (footprint "LQFP48")
      (description "单片机")
      (libsource (lib "PCB_Project") (part "CH559L"))
    )
    (comp (ref "U11")
      (value "AP2191WG-7")
      (footprint "SOT23-5")
      (libsource (lib "AIWAC-bolsterV01") (part "AP2191WG-7"))
    )
    (comp (ref "U12")
      (value "AP2191WG-7")
      (footprint "SOT23-5")
      (libsource (lib "AIWAC-bolsterV01") (part "AP2191WG-7"))
    )
    (comp (ref "Y1")
      (value "26MHz")
      (footprint "Y-CPX-32GA-4P")
      (description "晶振-贴片无源")
      (libsource (lib "Others") (part "YC-26MHz"))
    )
  )
  (nets
    (net (code "1") (name "/AP-CK32KO") (class "Default")
      (node (ref "R66") (pin "2") (pinfunction "2_2") (pintype "passive"))
      (node (ref "R68") (pin "2") (pinfunction "2_2") (pintype "passive"))
      (node (ref "U1") (pin "110") (pinfunction "AP-CK32KO_110") (pintype "passive"))
    )
    (net (code "2") (name "/AP-UART1-CTS") (class "Default")
      (node (ref "U1") (pin "38") (pinfunction "AP-UART1-CTS/PG9_38") (pintype "passive"))
      (node (ref "U9") (pin "41") (pinfunction "UART_RTS_N_41") (pintype "passive"))
    )
    (net (code "3") (name "/AP-UART1-RTS") (class "Default")
      (node (ref "U1") (pin "37") (pinfunction "AP-UART1-RTS/PG8_37") (pintype "passive"))
      (node (ref "U9") (pin "44") (pinfunction "UART_CTS_N_44") (pintype "passive"))
    )
    (net (code "4") (name "/AP-UART1-RX") (class "Default")
      (node (ref "R59") (pin "2") (pinfunction "2_2") (pintype "passive"))
      (node (ref "U1") (pin "35") (pinfunction "AP-UART1-RX/PG7_35") (pintype "passive"))
      (node (ref "U9") (pin "42") (pinfunction "UART_TXD_42") (pintype "passive"))
    )
    (net (code "5") (name "/AP-UART1-TX") (class "Default")
      (node (ref "R60") (pin "2") (pinfunction "2_2") (pintype "passive"))
      (node (ref "U1") (pin "36") (pinfunction "AP-UART1-TX/PG6_36") (pintype "passive"))
      (node (ref "U9") (pin "43") (pinfunction "UART_RXD_43") (pintype "passive"))
    )
    (net (code "6") (name "/B2") (class "Default")
      (node (ref "U1") (pin "102") (pinfunction "LCD-D2_102") (pintype "passive"))
      (node (ref "U6") (pin "3") (pinfunction "S1_3") (pintype "passive"))
    )
    (net (code "7") (name "/B3") (class "Default")
      (node (ref "U1") (pin "101") (pinfunction "LCD-D3_101") (pintype "passive"))
      (node (ref "U6") (pin "4") (pinfunction "S2_4") (pintype "passive"))
    )
    (net (code "8") (name "/B4") (class "Default")
      (node (ref "U1") (pin "100") (pinfunction "LCD-D4_100") (pintype "passive"))
      (node (ref "U6") (pin "5") (pinfunction "S3_5") (pintype "passive"))
    )
    (net (code "9") (name "/B5") (class "Default")
      (node (ref "U1") (pin "99") (pinfunction "LCD-D5_99") (pintype "passive"))
      (node (ref "U6") (pin "6") (pinfunction "S4_6") (pintype "passive"))
    )
    (net (code "10") (name "/B6") (class "Default")
      (node (ref "U1") (pin "98") (pinfunction "LCD-D6_98") (pintype "passive"))
      (node (ref "U6") (pin "7") (pinfunction "S5_7") (pintype "passive"))
    )
    (net (code "11") (name "/B7") (class "Default")
      (node (ref "U1") (pin "97") (pinfunction "LCD-D7_97") (pintype "passive"))
      (node (ref "U6") (pin "8") (pinfunction "S6_8") (pintype "passive"))
    )
    (net (code "12") (name "/BT-HOST-WAKE") (class "Default")
      (node (ref "U1") (pin "106") (pinfunction "BT-WAKE-AP/PL9_106") (pintype "passive"))
      (node (ref "U9") (pin "7") (pinfunction "BT_HOST_WAKE_7") (pintype "passive"))
    )
    (net (code "13") (name "/BT-RST-N") (class "Default")
      (node (ref "R61") (pin "1") (pinfunction "1_1") (pintype "passive"))
      (node (ref "U1") (pin "109") (pinfunction "BT-RST-N/PL8_109") (pintype "passive"))
      (node (ref "U9") (pin "34") (pinfunction "BT_RST_N_34") (pintype "passive"))
    )
    (net (code "14") (name "/BT-WAKE") (class "Default")
      (node (ref "R65") (pin "1") (pinfunction "1_1") (pintype "passive"))
      (node (ref "U1") (pin "105") (pinfunction "AP-WAKE-BT/PL10_105") (pintype "passive"))
      (node (ref "U9") (pin "6") (pinfunction "BT_WAKE_6") (pintype "passive"))
    )
    (net (code "15") (name "/CHGLED") (class "Default")
      (node (ref "R48") (pin "2") (pinfunction "2_2") (pintype "passive"))
      (node (ref "U1") (pin "120") (pinfunction "CHGLED_120") (pintype "passive"))
    )
    (net (code "16") (name "/DM") (class "Default")
      (node (ref "D23") (pin "2") (pinfunction "K_2") (pintype "passive"))
      (node (ref "J19") (pin "2") (pinfunction "2_2") (pintype "passive"))
      (node (ref "U10") (pin "32") (pinfunction "P5.0/DM_32") (pintype "bidirectional"))
    )
    (net (code "17") (name "/DP") (class "Default")
      (node (ref "D24") (pin "2") (pinfunction "K_2") (pintype "passive"))
      (node (ref "J19") (pin "3") (pinfunction "3_3") (pintype "passive"))
      (node (ref "U10") (pin "31") (pinfunction "P5.1/DP_31") (pintype "bidirectional"))
    )
    (net (code "18") (name "/ECH1") (class "Default")
      (node (ref "J4") (pin "3") (pinfunction "3_3") (pintype "passive"))
      (node (ref "L4") (pin "2") (pinfunction "2_2") (pintype "passive"))
      (node (ref "R20") (pin "1") (pinfunction "1_1") (pintype "passive"))
    )
    (net (code "19") (name "/ECH2") (class "Default")
      (node (ref "J5") (pin "3") (pinfunction "3_3") (pintype "passive"))
      (node (ref "L5") (pin "2") (pinfunction "2_2") (pintype "passive"))
      (node (ref "R17") (pin "1") (pinfunction "1_1") (pintype "passive"))
    )
    (net (code "20") (name "/ECH3") (class "Default")
      (node (ref "J8") (pin "3") (pinfunction "3_3") (pintype "passive"))
      (node (ref "L8") (pin "2") (pinfunction "2_2") (pintype "passive"))
      (node (ref "R16") (pin "1") (pinfunction "1_1") (pintype "passive"))
    )
    (net (code "21") (name "/ECH4") (class "Default")
      (node (ref "J9") (pin "3") (pinfunction "3_3") (pintype "passive"))
      (node (ref "L9") (pin "2") (pinfunction "2_2") (pintype "passive"))
      (node (ref "R15") (pin "1") (pinfunction "1_1") (pintype "passive"))
    )
    (net (code "22") (name "/G2") (class "Default")
      (node (ref "U1") (pin "96") (pinfunction "LCD-D10_96") (pintype "passive"))
      (node (ref "U6") (pin "9") (pinfunction "S7_9") (pintype "passive"))
    )
    (net (code "23") (name "/G3") (class "Default")
      (node (ref "U1") (pin "95") (pinfunction "LCD-D11_95") (pintype "passive"))
      (node (ref "U6") (pin "10") (pinfunction "S8_10") (pintype "passive"))
    )
    (net (code "24") (name "/G4") (class "Default")
      (node (ref "U1") (pin "94") (pinfunction "LCD-D12_94") (pintype "passive"))
    )
    (net (code "25") (name "/G5") (class "Default")
      (node (ref "U1") (pin "93") (pinfunction "LCD-D13_93") (pintype "passive"))
    )
    (net (code "26") (name "/G6") (class "Default")
      (node (ref "U1") (pin "92") (pinfunction "LCD-D14_92") (pintype "passive"))
    )
    (net (code "27") (name "/G7") (class "Default")
      (node (ref "U1") (pin "91") (pinfunction "LCD-D15_91") (pintype "passive"))
    )
    (net (code "28") (name "/HPL") (class "Default")
      (node (ref "C25") (pin "1") (pinfunction "1_1") (pintype "passive"))
      (node (ref "U1") (pin "118") (pinfunction "HPL_118") (pintype "passive"))
    )
    (net (code "29") (name "/HPR") (class "Default")
      (node (ref "C28") (pin "1") (pinfunction "1_1") (pintype "passive"))
      (node (ref "U1") (pin "119") (pinfunction "HPR_119") (pintype "passive"))
    )
    (net (code "30") (name "/INPUT1") (class "Default")
      (node (ref "R33") (pin "1") (pinfunction "1_1") (pintype "passive"))
      (node (ref "U4") (pin "2") (pinfunction "INPUT1_2") (pintype "passive"))
    )
    (net (code "31") (name "/INPUT2") (class "Default")
      (node (ref "R34") (pin "1") (pinfunction "1_1") (pintype "passive"))
      (node (ref "U4") (pin "9") (pinfunction "INPUT2_9") (pintype "passive"))
    )
    (net (code "32") (name "/INPUT3") (class "Default")
      (node (ref "R35") (pin "1") (pinfunction "1_1") (pintype "passive"))
      (node (ref "U4") (pin "12") (pinfunction "INPUT3_12") (pintype "passive"))
    )
    (net (code "33") (name "/INPUT4") (class "Default")
      (node (ref "R36") (pin "1") (pinfunction "1_1") (pintype "passive"))
      (node (ref "U4") (pin "19") (pinfunction "INPUT4_19") (pintype "passive"))
    )
    (net (code "34") (name "/INPUT5") (class "Default")
      (node (ref "R37") (pin "1") (pinfunction "1_1") (pintype "passive"))
      (node (ref "U5") (pin "2") (pinfunction "INPUT1_2") (pintype "passive"))
    )
    (net (code "35") (name "/INPUT6") (class "Default")
      (node (ref "R38") (pin "1") (pinfunction "1_1") (pintype "passive"))
      (node (ref "U5") (pin "9") (pinfunction "INPUT2_9") (pintype "passive"))
    )
    (net (code "36") (name "/INPUT7") (class "Default")
      (node (ref "R39") (pin "1") (pinfunction "1_1") (pintype "passive"))
      (node (ref "U5") (pin "12") (pinfunction "INPUT3_12") (pintype "passive"))
    )
    (net (code "37") (name "/INPUT8") (class "Default")
      (node (ref "R40") (pin "1") (pinfunction "1_1") (pintype "passive"))
      (node (ref "U5") (pin "19") (pinfunction "INPUT4_19") (pintype "passive"))
    )
    (net (code "38") (name "/LCD-BL-EN") (class "Default")
      (node (ref "J2") (pin "33") (pinfunction "33_33") (pintype "passive"))
      (node (ref "U1") (pin "47") (pinfunction "LCD-BL-EN/PB7_47") (pintype "passive"))
    )
    (net (code "39") (name "/LCD-PWM") (class "Default")
      (node (ref "J2") (pin "32") (pinfunction "32_32") (pintype "passive"))
      (node (ref "U1") (pin "30") (pinfunction "LCD-PWM/PH0_30") (pintype "passive"))
    )
    (net (code "40") (name "/LCDS0_VN3") (class "Default")
      (node (ref "J2") (pin "29") (pinfunction "29_29") (pintype "passive"))
      (node (ref "U1") (pin "81") (pinfunction "LCD-VSYNC_81") (pintype "passive"))
    )
    (net (code "41") (name "/LCDS0_VP3") (class "Default")
      (node (ref "J2") (pin "30") (pinfunction "30_30") (pintype "passive"))
      (node (ref "U1") (pin "82") (pinfunction "LCD-HSYNC_82") (pintype "passive"))
    )
    (net (code "42") (name "/LRADC0") (class "Default")
      (node (ref "R58") (pin "2") (pinfunction "2_2") (pintype "passive"))
      (node (ref "R63") (pin "1") (pinfunction "1_1") (pintype "passive"))
      (node (ref "U1") (pin "115") (pinfunction "LRADC0_115") (pintype "passive"))
    )
    (net (code "43") (name "/LVDS0_VN0") (class "Default")
      (node (ref "J2") (pin "23") (pinfunction "23_23") (pintype "passive"))
      (node (ref "U1") (pin "89") (pinfunction "LCD-D19_89") (pintype "passive"))
    )
    (net (code "44") (name "/LVDS0_VN1") (class "Default")
      (node (ref "J2") (pin "25") (pinfunction "25_25") (pintype "passive"))
      (node (ref "U1") (pin "87") (pinfunction "LCD-D21_87") (pintype "passive"))
    )
    (net (code "45") (name "/LVDS0_VN2") (class "Default")
      (node (ref "J2") (pin "27") (pinfunction "27_27") (pintype "passive"))
      (node (ref "U1") (pin "85") (pinfunction "LCD-D23_85") (pintype "passive"))
    )
    (net (code "46") (name "/LVDS0_VNC") (class "Default")
      (node (ref "J2") (pin "31") (pinfunction "31_31") (pintype "passive"))
      (node (ref "U1") (pin "83") (pinfunction "LCD-DE_83") (pintype "passive"))
    )
    (net (code "47") (name "/LVDS0_VP0") (class "Default")
      (node (ref "J2") (pin "22") (pinfunction "22_22") (pintype "passive"))
      (node (ref "U1") (pin "90") (pinfunction "LCD-D18_90") (pintype "passive"))
    )
    (net (code "48") (name "/LVDS0_VP1") (class "Default")
      (node (ref "J2") (pin "24") (pinfunction "24_24") (pintype "passive"))
      (node (ref "U1") (pin "88") (pinfunction "LCD-D20_88") (pintype "passive"))
    )
    (net (code "49") (name "/LVDS0_VP2") (class "Default")
      (node (ref "J2") (pin "26") (pinfunction "26_26") (pintype "passive"))
      (node (ref "U1") (pin "86") (pinfunction "LCD-D22_86") (pintype "passive"))
    )
    (net (code "50") (name "/LVDS0_VPC") (class "Default")
      (node (ref "J2") (pin "28") (pinfunction "28_28") (pintype "passive"))
      (node (ref "U1") (pin "84") (pinfunction "LCD-CLK_84") (pintype "passive"))
    )
    (net (code "51") (name "/MCLK-IN") (class "Default")
      (node (ref "R44") (pin "1") (pinfunction "1_1") (pintype "passive"))
      (node (ref "U9") (pin "30") (pinfunction "TCXO_IN_30") (pintype "passive"))
    )
    (net (code "52") (name "/MIC+") (class "Default")
      (node (ref "C22") (pin "2") (pinfunction "2_2") (pintype "passive"))
      (node (ref "C24") (pin "1") (pinfunction "1_1") (pintype "passive"))
      (node (ref "J12") (pin "1") (pinfunction "1_1") (pintype "passive"))
      (node (ref "U1") (pin "116") (pinfunction "MIC+_116") (pintype "passive"))
    )
    (net (code "53") (name "/MIC-") (class "Default")
      (node (ref "C24") (pin "2") (pinfunction "2_2") (pintype "passive"))
      (node (ref "C26") (pin "1") (pinfunction "1_1") (pintype "passive"))
      (node (ref "J12") (pin "2") (pinfunction "2_2") (pintype "passive"))
      (node (ref "U1") (pin "117") (pinfunction "MIC-_117") (pintype "passive"))
    )
    (net (code "54") (name "/OUTPUT1") (class "Default")
      (node (ref "D1") (pin "1") (pinfunction "1_1") (pintype "passive"))
      (node (ref "D5") (pin "2") (pinfunction "2_2") (pintype "passive"))
      (node (ref "J7") (pin "1") (pinfunction "1_1") (pintype "passive"))
      (node (ref "U4") (pin "3") (pinfunction "OUTPUT1_3") (pintype "passive"))
    )
    (net (code "55") (name "/OUTPUT2") (class "Default")
      (node (ref "D13") (pin "2") (pinfunction "2_2") (pintype "passive"))
      (node (ref "D9") (pin "1") (pinfunction "1_1") (pintype "passive"))
      (node (ref "J7") (pin "2") (pinfunction "2_2") (pintype "passive"))
      (node (ref "U4") (pin "8") (pinfunction "OUTPUT2_8") (pintype "passive"))
    )
    (net (code "56") (name "/OUTPUT3") (class "Default")
      (node (ref "D10") (pin "1") (pinfunction "1_1") (pintype "passive"))
      (node (ref "D15") (pin "2") (pinfunction "2_2") (pintype "passive"))
      (node (ref "J10") (pin "1") (pinfunction "1_1") (pintype "passive"))
      (node (ref "U4") (pin "13") (pinfunction "OUTPUT3_13") (pintype "passive"))
    )
    (net (code "57") (name "/OUTPUT4") (class "Default")
      (node (ref "D2") (pin "1") (pinfunction "1_1") (pintype "passive"))
      (node (ref "D6") (pin "2") (pinfunction "2_2") (pintype "passive"))
      (node (ref "J10") (pin "2") (pinfunction "2_2") (pintype "passive"))
      (node (ref "U4") (pin "18") (pinfunction "OUTPUT4_18") (pintype "passive"))
    )
    (net (code "58") (name "/OUTPUT5") (class "Default")
      (node (ref "D3") (pin "1") (pinfunction "1_1") (pintype "passive"))
      (node (ref "D7") (pin "2") (pinfunction "2_2") (pintype "passive"))
      (node (ref "J6") (pin "1") (pinfunction "1_1") (pintype "passive"))
      (node (ref "U5") (pin "3") (pinfunction "OUTPUT1_3") (pintype "passive"))
    )
    (net (code "59") (name "/OUTPUT6") (class "Default")
      (node (ref "D11") (pin "1") (pinfunction "1_1") (pintype "passive"))
      (node (ref "D14") (pin "2") (pinfunction "2_2") (pintype "passive"))
      (node (ref "J6") (pin "2") (pinfunction "2_2") (pintype "passive"))
      (node (ref "U5") (pin "8") (pinfunction "OUTPUT2_8") (pintype "passive"))
    )
    (net (code "60") (name "/OUTPUT7") (class "Default")
      (node (ref "D12") (pin "1") (pinfunction "1_1") (pintype "passive"))
      (node (ref "D16") (pin "2") (pinfunction "2_2") (pintype "passive"))
      (node (ref "J11") (pin "1") (pinfunction "1_1") (pintype "passive"))
      (node (ref "U5") (pin "13") (pinfunction "OUTPUT3_13") (pintype "passive"))
    )
    (net (code "61") (name "/OUTPUT8") (class "Default")
      (node (ref "D4") (pin "1") (pinfunction "1_1") (pintype "passive"))
      (node (ref "D8") (pin "2") (pinfunction "2_2") (pintype "passive"))
      (node (ref "J11") (pin "2") (pinfunction "2_2") (pintype "passive"))
      (node (ref "U5") (pin "18") (pinfunction "OUTPUT4_18") (pintype "passive"))
    )
    (net (code "62") (name "/P0.0") (class "Default")
      (node (ref "U10") (pin "40") (pinfunction "P0.0/AD0/UDTR_40") (pintype "bidirectional"))
      (node (ref "U3") (pin "9") (pinfunction "S7_9") (pintype "passive"))
    )
    (net (code "63") (name "/P0.1") (class "Default")
      (node (ref "U10") (pin "39") (pinfunction "P0.1/AD1/URTS_39") (pintype "bidirectional"))
      (node (ref "U3") (pin "10") (pinfunction "S8_10") (pintype "passive"))
    )
    (net (code "64") (name "/P0.4") (class "Default")
      (node (ref "C21") (pin "1") (pinfunction "1_1") (pintype "passive"))
      (node (ref "L13") (pin "2") (pinfunction "2_2") (pintype "passive"))
      (node (ref "R41") (pin "1") (pinfunction "1_1") (pintype "passive"))
      (node (ref "R42") (pin "1") (pinfunction "1_1") (pintype "passive"))
      (node (ref "SW1") (pin "1") (pinfunction "1_1") (pintype "passive"))
      (node (ref "U10") (pin "36") (pinfunction "P0.4/AD4/UCTS_36") (pintype "bidirectional"))
    )
    (net (code "65") (name "/P0.5") (class "Default")
      (node (ref "C27") (pin "1") (pinfunction "1_1") (pintype "passive"))
      (node (ref "L15") (pin "2") (pinfunction "2_2") (pintype "passive"))
      (node (ref "R47") (pin "1") (pinfunction "1_1") (pintype "passive"))
      (node (ref "R51") (pin "1") (pinfunction "1_1") (pintype "passive"))
      (node (ref "SW2") (pin "1") (pinfunction "1_1") (pintype "passive"))
      (node (ref "U10") (pin "35") (pinfunction "P0.5/AD5/UDSR_35") (pintype "bidirectional"))
    )
    (net (code "66") (name "/P0.6") (class "Default")
      (node (ref "C35") (pin "1") (pinfunction "1_1") (pintype "passive"))
      (node (ref "L17") (pin "2") (pinfunction "2_2") (pintype "passive"))
      (node (ref "R54") (pin "1") (pinfunction "1_1") (pintype "passive"))
      (node (ref "R56") (pin "1") (pinfunction "1_1") (pintype "passive"))
      (node (ref "SW3") (pin "1") (pinfunction "1_1") (pintype "passive"))
      (node (ref "U10") (pin "34") (pinfunction "P0.6/AD6/URI_34") (pintype "bidirectional"))
    )
    (net (code "67") (name "/P0.7") (class "Default")
      (node (ref "C37") (pin "1") (pinfunction "1_1") (pintype "passive"))
      (node (ref "L18") (pin "2") (pinfunction "2_2") (pintype "passive"))
      (node (ref "R57") (pin "1") (pinfunction "1_1") (pintype "passive"))
      (node (ref "R62") (pin "1") (pinfunction "1_1") (pintype "passive"))
      (node (ref "SW4") (pin "1") (pinfunction "1_1") (pintype "passive"))
      (node (ref "U10") (pin "33") (pinfunction "P0.7/AD7/UDCD_33") (pintype "bidirectional"))
    )
    (net (code "68") (name "/P1.0") (class "Default")
      (node (ref "U10") (pin "43") (pinfunction "P1.0/AIN0/T2/CAP1_43") (pintype "bidirectional"))
      (node (ref "U3") (pin "8") (pinfunction "S6_8") (pintype "passive"))
    )
    (net (code "69") (name "/P1.1") (class "Default")
      (node (ref "U10") (pin "44") (pinfunction "P1.1/AIN1/T2EX/CAP2_44") (pintype "bidirectional"))
      (node (ref "U3") (pin "7") (pinfunction "S5_7") (pintype "passive"))
    )
    (net (code "70") (name "/P1.2") (class "Default")
      (node (ref "U10") (pin "45") (pinfunction "P1.2/AIN2/PWM3/CAP3_45") (pintype "bidirectional"))
      (node (ref "U3") (pin "6") (pinfunction "S4_6") (pintype "passive"))
    )
    (net (code "71") (name "/P1.3") (class "Default")
      (node (ref "U10") (pin "46") (pinfunction "P1.3/AIN3_46") (pintype "bidirectional"))
      (node (ref "U3") (pin "5") (pinfunction "S3_5") (pintype "passive"))
    )
    (net (code "72") (name "/P1.4") (class "Default")
      (node (ref "U10") (pin "47") (pinfunction "P1.4/AIN4/SCS_47") (pintype "bidirectional"))
      (node (ref "U3") (pin "4") (pinfunction "S2_4") (pintype "passive"))
    )
    (net (code "73") (name "/P1.5") (class "Default")
      (node (ref "U10") (pin "48") (pinfunction "P1.5/AIN5/MOSI_48") (pintype "bidirectional"))
      (node (ref "U3") (pin "3") (pinfunction "S1_3") (pintype "passive"))
    )
    (net (code "74") (name "/PB6") (class "Default")
      (node (ref "U1") (pin "48") (pinfunction "PB6_48") (pintype "passive"))
    )
    (net (code "75") (name "/PE0_CSI-PCLK") (class "Default")
      (node (ref "J1") (pin "7") (pinfunction "7_7") (pintype "passive"))
      (node (ref "U1") (pin "63") (pinfunction "PE0_CSI-PCLK_63") (pintype "passive"))
    )
    (net (code "76") (name "/PE1_CSI-MCLK") (class "Default")
      (node (ref "J1") (pin "11") (pinfunction "11_11") (pintype "passive"))
      (node (ref "U1") (pin "64") (pinfunction "PE1_CSI-MCLK_64") (pintype "passive"))
    )
    (net (code "77") (name "/PE2_CSI-HSYNC") (class "Default")
      (node (ref "J3") (pin "8") (pinfunction "8_8") (pintype "passive"))
      (node (ref "U1") (pin "65") (pinfunction "PE2_CSI-HSYNC_65") (pintype "passive"))
    )
    (net (code "78") (name "/PE3_CSI-VSYNC") (class "Default")
      (node (ref "J3") (pin "6") (pinfunction "6_6") (pintype "passive"))
      (node (ref "U1") (pin "66") (pinfunction "PE3_CSI-VSYNC_66") (pintype "passive"))
    )
    (net (code "79") (name "/PE4_CSI-D0") (class "Default")
      (node (ref "J1") (pin "5") (pinfunction "5_5") (pintype "passive"))
      (node (ref "U1") (pin "67") (pinfunction "PE4_CSI-D0_67") (pintype "passive"))
    )
    (net (code "80") (name "/PE5_CSI-D1") (class "Default")
      (node (ref "J1") (pin "3") (pinfunction "3_3") (pintype "passive"))
      (node (ref "U1") (pin "68") (pinfunction "PE5_CSI-D1_68") (pintype "passive"))
    )
    (net (code "81") (name "/PE6_CSI-D2") (class "Default")
      (node (ref "J1") (pin "2") (pinfunction "2_2") (pintype "passive"))
      (node (ref "U1") (pin "69") (pinfunction "PE6_CSI-D2_69") (pintype "passive"))
    )
    (net (code "82") (name "/PE7_CSI-D3") (class "Default")
      (node (ref "J1") (pin "4") (pinfunction "4_4") (pintype "passive"))
      (node (ref "U1") (pin "70") (pinfunction "PE7_CSI-D3_70") (pintype "passive"))
    )
    (net (code "83") (name "/PE8_CSI-D4") (class "Default")
      (node (ref "J1") (pin "6") (pinfunction "6_6") (pintype "passive"))
      (node (ref "U1") (pin "71") (pinfunction "PE8_CSI-D4_71") (pintype "passive"))
    )
    (net (code "84") (name "/PE9_CSI-D5") (class "Default")
      (node (ref "J1") (pin "8") (pinfunction "8_8") (pintype "passive"))
      (node (ref "U1") (pin "72") (pinfunction "PE9_CSI-D5_72") (pintype "passive"))
    )
    (net (code "85") (name "/PE10_CSI-D6") (class "Default")
      (node (ref "J1") (pin "10") (pinfunction "10_10") (pintype "passive"))
      (node (ref "U1") (pin "73") (pinfunction "PE10_CSI-D6_73") (pintype "passive"))
    )
    (net (code "86") (name "/PE11_CSI-D7") (class "Default")
      (node (ref "J3") (pin "11") (pinfunction "11_11") (pintype "passive"))
      (node (ref "U1") (pin "74") (pinfunction "PE11_CSI-D7_74") (pintype "passive"))
    )
    (net (code "87") (name "/PE12_CSI-SCK") (class "Default")
      (node (ref "J3") (pin "4") (pinfunction "4_4") (pintype "passive"))
      (node (ref "U1") (pin "75") (pinfunction "PE12_CSI-SCK_75") (pintype "passive"))
    )
    (net (code "88") (name "/PE13_CSI-SDA") (class "Default")
      (node (ref "J3") (pin "2") (pinfunction "2_2") (pintype "passive"))
      (node (ref "U1") (pin "76") (pinfunction "PE13_CSI-SDA_76") (pintype "passive"))
    )
    (net (code "89") (name "/PE16_CSI-RST-F") (class "Default")
      (node (ref "J3") (pin "5") (pinfunction "5_5") (pintype "passive"))
      (node (ref "R7") (pin "2") (pinfunction "2_2") (pintype "passive"))
      (node (ref "U1") (pin "79") (pinfunction "PE16_CSI-RST-F_79") (pintype "passive"))
    )
    (net (code "90") (name "/PE17_CSI-STBY-F") (class "Default")
      (node (ref "J3") (pin "7") (pinfunction "7_7") (pintype "passive"))
      (node (ref "R6") (pin "1") (pinfunction "1_1") (pintype "passive"))
      (node (ref "U1") (pin "80") (pinfunction "PE17_CSI-STBY-F_80") (pintype "passive"))
    )
    (net (code "91") (name "/PH4-SCK1") (class "Default")
      (node (ref "U1") (pin "49") (pinfunction "SCK1/PH4_49") (pintype "passive"))
    )
    (net (code "92") (name "/PH5-SDA1") (class "Default")
      (node (ref "U1") (pin "50") (pinfunction "SDA1/PH5_50") (pintype "passive"))
    )
    (net (code "93") (name "/POWERKEY") (class "Default")
      (node (ref "J20") (pin "1") (pinfunction "1_1") (pintype "passive"))
      (node (ref "U1") (pin "14") (pinfunction "POWERKEY_14") (pintype "passive"))
    )
    (net (code "94") (name "/SDC0-CLK") (class "Default")
      (node (ref "J16") (pin "6") (pinfunction "CLK_6") (pintype "passive"))
      (node (ref "J30") (pin "1") (pinfunction "1_1") (pintype "passive"))
      (node (ref "U1") (pin "58") (pinfunction "SDC0-CLK/UART0-TX/PF2_58") (pintype "passive"))
    )
    (net (code "95") (name "/SDC0-CMD") (class "Default")
      (node (ref "J16") (pin "4") (pinfunction "CMD_4") (pintype "power_in"))
      (node (ref "U1") (pin "57") (pinfunction "SDC0-CMD/PF3_57") (pintype "passive"))
    )
    (net (code "96") (name "/SDC0-D0") (class "Default")
      (node (ref "J16") (pin "8") (pinfunction "DAT0_8") (pintype "passive"))
      (node (ref "U1") (pin "53") (pinfunction "SDC0-D0/PF1_53") (pintype "passive"))
    )
    (net (code "97") (name "/SDC0-D1") (class "Default")
      (node (ref "J16") (pin "9") (pinfunction "DAT1_9") (pintype "passive"))
      (node (ref "U1") (pin "54") (pinfunction "SDC0-D1/PF0_54") (pintype "passive"))
    )
    (net (code "98") (name "/SDC0-D2") (class "Default")
      (node (ref "J16") (pin "2") (pinfunction "DAT2_2") (pintype "power_in"))
      (node (ref "U1") (pin "55") (pinfunction "SDC0-D2/PF5_55") (pintype "passive"))
    )
    (net (code "99") (name "/SDC0-D3") (class "Default")
      (node (ref "J16") (pin "3") (pinfunction "DAT3_3") (pintype "power_in"))
      (node (ref "J30") (pin "2") (pinfunction "2_2") (pintype "passive"))
      (node (ref "U1") (pin "56") (pinfunction "SDC0-D3/UART0-RX/PF4_56") (pintype "passive"))
    )
    (net (code "100") (name "/SDIO-CLK") (class "Default")
      (node (ref "R74") (pin "2") (pinfunction "2_2") (pintype "passive"))
      (node (ref "U1") (pin "42") (pinfunction "WL-SDIO-CLK/PG0_42") (pintype "passive"))
    )
    (net (code "101") (name "/SDIO-CMD") (class "Default")
      (node (ref "R77") (pin "2") (pinfunction "2_2") (pintype "passive"))
      (node (ref "U1") (pin "41") (pinfunction "WL-SDIO-CMD/PG1_41") (pintype "passive"))
      (node (ref "U9") (pin "16") (pinfunction "SDIO_DATA_CMD_16") (pintype "passive"))
    )
    (net (code "102") (name "/SDIO-D0") (class "Default")
      (node (ref "R78") (pin "2") (pinfunction "2_2") (pintype "passive"))
      (node (ref "U1") (pin "43") (pinfunction "WL-SDIO-D0/PG2_43") (pintype "passive"))
      (node (ref "U9") (pin "18") (pinfunction "SDIO_DATA_0_18") (pintype "passive"))
    )
    (net (code "103") (name "/SDIO-D1") (class "Default")
      (node (ref "R79") (pin "2") (pinfunction "2_2") (pintype "passive"))
      (node (ref "U1") (pin "44") (pinfunction "WL-SDIO-D1/PG3_44") (pintype "passive"))
      (node (ref "U9") (pin "19") (pinfunction "SDIO_DATA_1_19") (pintype "passive"))
    )
    (net (code "104") (name "/SDIO-D2") (class "Default")
      (node (ref "R75") (pin "2") (pinfunction "2_2") (pintype "passive"))
      (node (ref "U1") (pin "45") (pinfunction "WL-SDIO-D2/PG4_45") (pintype "passive"))
      (node (ref "U9") (pin "14") (pinfunction "SDIO_DATA_2_14") (pintype "passive"))
    )
    (net (code "105") (name "/SDIO-D3") (class "Default")
      (node (ref "R76") (pin "2") (pinfunction "2_2") (pintype "passive"))
      (node (ref "U1") (pin "46") (pinfunction "WL-SDIO-D3/PG5_46") (pintype "passive"))
      (node (ref "U9") (pin "15") (pinfunction "SDIO_DATA_3_15") (pintype "passive"))
    )
    (net (code "106") (name "/SPI0-CLK") (class "Default")
      (node (ref "U1") (pin "61") (pinfunction "SPI0-CLK/PC2_61") (pintype "passive"))
    )
    (net (code "107") (name "/SPI0-CS") (class "Default")
      (node (ref "U1") (pin "62") (pinfunction "SPI0-CS/PC3_62") (pintype "passive"))
    )
    (net (code "108") (name "/SPI0-MISO") (class "Default")
      (node (ref "U1") (pin "59") (pinfunction "SPI0-MISO/PC1_59") (pintype "passive"))
    )
    (net (code "109") (name "/SPI0-MOSI") (class "Default")
      (node (ref "U1") (pin "60") (pinfunction "SPI0-MOSI/PC0_60") (pintype "passive"))
    )
    (net (code "110") (name "/T-CARD-DET") (class "Default")
      (node (ref "J16") (pin "10") (pinfunction "CD#_10") (pintype "passive"))
      (node (ref "U1") (pin "52") (pinfunction "T-CARD-DET/PB4_52") (pintype "passive"))
    )
    (net (code "111") (name "/TP-INT") (class "Default")
      (node (ref "J2") (pin "37") (pinfunction "37_37") (pintype "passive"))
      (node (ref "U1") (pin "34") (pinfunction "TP-INT/PB5_34") (pintype "passive"))
    )
    (net (code "112") (name "/TP-RST") (class "Default")
      (node (ref "J2") (pin "40") (pinfunction "40_40") (pintype "passive"))
      (node (ref "U1") (pin "31") (pinfunction "TP-RST/PH1_31") (pintype "passive"))
    )
    (net (code "113") (name "/TP-SCK") (class "Default")
      (node (ref "J2") (pin "39") (pinfunction "39_39") (pintype "passive"))
      (node (ref "R9") (pin "2") (pinfunction "2_2") (pintype "passive"))
      (node (ref "U1") (pin "32") (pinfunction "TP-SCK/PH2_32") (pintype "passive"))
    )
    (net (code "114") (name "/TP-SDA") (class "Default")
      (node (ref "J2") (pin "38") (pinfunction "38_38") (pintype "passive"))
      (node (ref "R8") (pin "2") (pinfunction "2_2") (pintype "passive"))
      (node (ref "U1") (pin "33") (pinfunction "TP-SDA/PH3_33") (pintype "passive"))
    )
    (net (code "115") (name "/TRI1") (class "Default")
      (node (ref "J4") (pin "2") (pinfunction "2_2") (pintype "passive"))
      (node (ref "L6") (pin "2") (pinfunction "2_2") (pintype "passive"))
      (node (ref "R27") (pin "1") (pinfunction "1_1") (pintype "passive"))
    )
    (net (code "116") (name "/TRI2") (class "Default")
      (node (ref "J5") (pin "2") (pinfunction "2_2") (pintype "passive"))
      (node (ref "L7") (pin "2") (pinfunction "2_2") (pintype "passive"))
      (node (ref "R26") (pin "1") (pinfunction "1_1") (pintype "passive"))
    )
    (net (code "117") (name "/TRI3") (class "Default")
      (node (ref "J8") (pin "2") (pinfunction "2_2") (pintype "passive"))
      (node (ref "L10") (pin "2") (pinfunction "2_2") (pintype "passive"))
      (node (ref "R22") (pin "1") (pinfunction "1_1") (pintype "passive"))
    )
    (net (code "118") (name "/TRI4") (class "Default")
      (node (ref "J9") (pin "2") (pinfunction "2_2") (pintype "passive"))
      (node (ref "L11") (pin "2") (pinfunction "2_2") (pintype "passive"))
      (node (ref "R21") (pin "1") (pinfunction "1_1") (pintype "passive"))
    )
    (net (code "119") (name "/Temp") (class "Default")
      (node (ref "C33") (pin "1") (pinfunction "1_1") (pintype "passive"))
      (node (ref "R53") (pin "1") (pinfunction "1_1") (pintype "passive"))
      (node (ref "R55") (pin "2") (pinfunction "2_2") (pintype "passive"))
      (node (ref "U1") (pin "5") (pinfunction "TS_5") (pintype "passive"))
    )
    (net (code "120") (name "/UART2_CTS") (class "Default")
      (node (ref "R80") (pin "1") (pinfunction "1_1") (pintype "passive"))
      (node (ref "U1") (pin "25") (pinfunction "UART2-CTS/PB3_25") (pintype "passive"))
    )
    (net (code "121") (name "/UART2_RX") (class "Default")
      (node (ref "J40") (pin "2") (pinfunction "2_2") (pintype "passive"))
      (node (ref "U1") (pin "23") (pinfunction "UART2-RX/PB1_23") (pintype "passive"))
    )
    (net (code "122") (name "/UART2_TX") (class "Default")
      (node (ref "J40") (pin "1") (pinfunction "1_1") (pintype "passive"))
      (node (ref "U1") (pin "24") (pinfunction "UART2-TX/PB0_24") (pintype "passive"))
    )
    (net (code "123") (name "/USB-DM0") (class "Default")
      (node (ref "D22") (pin "2") (pinfunction "K_2") (pintype "passive"))
      (node (ref "J18") (pin "2") (pinfunction "2_2") (pintype "passive"))
      (node (ref "U1") (pin "113") (pinfunction "USB-DM0_113") (pintype "passive"))
    )
    (net (code "124") (name "/USB-DM1") (class "Default")
      (node (ref "D19") (pin "1") (pinfunction "A_1") (pintype "passive"))
      (node (ref "J15") (pin "2") (pinfunction "2_2") (pintype "passive"))
      (node (ref "U1") (pin "111") (pinfunction "USB-DM1_111") (pintype "passive"))
    )
    (net (code "125") (name "/USB-DP0") (class "Default")
      (node (ref "D21") (pin "2") (pinfunction "K_2") (pintype "passive"))
      (node (ref "J18") (pin "3") (pinfunction "3_3") (pintype "passive"))
      (node (ref "U1") (pin "114") (pinfunction "USB-DP0_114") (pintype "passive"))
    )
    (net (code "126") (name "/USB-DP1") (class "Default")
      (node (ref "D20") (pin "1") (pinfunction "A_1") (pintype "passive"))
      (node (ref "J15") (pin "3") (pinfunction "3_3") (pintype "passive"))
      (node (ref "U1") (pin "112") (pinfunction "USB-DP1_112") (pintype "passive"))
    )
    (net (code "127") (name "/USB-DRVVBUS") (class "Default")
      (node (ref "R67") (pin "1") (pinfunction "1_1") (pintype "passive"))
      (node (ref "U1") (pin "21") (pinfunction "USB-DRVVBUS_21") (pintype "passive"))
    )
    (net (code "128") (name "/USB-ID") (class "Default")
      (node (ref "R83") (pin "1") (pinfunction "1_1") (pintype "passive"))
      (node (ref "U1") (pin "29") (pinfunction "USB-ID/PH8_29") (pintype "passive"))
    )
    (net (code "129") (name "/WL-HOST-WAKE") (class "Default")
      (node (ref "U1") (pin "108") (pinfunction "WL-WAKE-AP/PL7_108") (pintype "passive"))
      (node (ref "U9") (pin "13") (pinfunction "WL_HOST_WAKE_13") (pintype "passive"))
    )
    (net (code "130") (name "/WL-REG-ON") (class "Default")
      (node (ref "R73") (pin "1") (pinfunction "1_1") (pintype "passive"))
      (node (ref "U1") (pin "107") (pinfunction "WL-PMU-EN/PL6_107") (pintype "passive"))
      (node (ref "U9") (pin "12") (pinfunction "WL_REG_ON_12") (pintype "passive"))
    )
    (net (code "131") (name "ACIN5V") (class "Default")
      (node (ref "J2") (pin "1") (pinfunction "1_1") (pintype "passive"))
      (node (ref "J2") (pin "2") (pinfunction "2_2") (pintype "passive"))
      (node (ref "J2") (pin "3") (pinfunction "3_3") (pintype "passive"))
      (node (ref "J2") (pin "4") (pinfunction "4_4") (pintype "passive"))
      (node (ref "L1") (pin "2") (pinfunction "2_2") (pintype "passive"))
      (node (ref "L2") (pin "1") (pinfunction "1_1") (pintype "passive"))
      (node (ref "U1") (pin "15") (pinfunction "ACIN5V_15") (pintype "passive"))
      (node (ref "U1") (pin "16") (pinfunction "ACIN5V_16") (pintype "passive"))
    )
    (net (code "132") (name "AGND") (class "Default")
      (node (ref "C23") (pin "2") (pinfunction "2_2") (pintype "passive"))
      (node (ref "C30") (pin "2") (pinfunction "2_2") (pintype "passive"))
      (node (ref "L12") (pin "2") (pinfunction "2_2") (pintype "passive"))
      (node (ref "U8") (pin "8") (pinfunction "GND_8") (pintype "passive"))
    )
    (net (code "133") (name "AVDD-CSI") (class "Default")
      (node (ref "C3") (pin "1") (pinfunction "1_1") (pintype "passive"))
      (node (ref "J3") (pin "3") (pinfunction "3_3") (pintype "passive"))
      (node (ref "U1") (pin "8") (pinfunction "AVDD-CSI_8") (pintype "passive"))
    )
    (net (code "134") (name "DC5V") (class "Default")
      (node (ref "C15") (pin "1") (pinfunction "1_1") (pintype "passive"))
      (node (ref "C16") (pin "1") (pinfunction "1_1") (pintype "passive"))
      (node (ref "C18") (pin "2") (pinfunction "2_2") (pintype "passive"))
      (node (ref "C19") (pin "2") (pinfunction "2_2") (pintype "passive"))
      (node (ref "C44") (pin "2") (pinfunction "2_2") (pintype "passive"))
      (node (ref "C49") (pin "2") (pinfunction "2_2") (pintype "passive"))
      (node (ref "C55") (pin "1") (pinfunction "1_1") (pintype "passive"))
      (node (ref "C56") (pin "1") (pinfunction "1_1") (pintype "passive"))
      (node (ref "C57") (pin "2") (pinfunction "2_2") (pintype "passive"))
      (node (ref "C7") (pin "1") (pinfunction "1_1") (pintype "passive"))
      (node (ref "C8") (pin "2") (pinfunction "2_2") (pintype "passive"))
      (node (ref "C9") (pin "2") (pinfunction "2_2") (pintype "passive"))
      (node (ref "J19") (pin "1") (pinfunction "1_1") (pintype "passive"))
      (node (ref "L1") (pin "1") (pinfunction "1_1") (pintype "passive"))
      (node (ref "R28") (pin "2") (pinfunction "2_2") (pintype "passive"))
      (node (ref "R29") (pin "1") (pinfunction "1_1") (pintype "passive"))
      (node (ref "R3") (pin "2") (pinfunction "2_2") (pintype "passive"))
      (node (ref "R30") (pin "2") (pinfunction "2_2") (pintype "passive"))
      (node (ref "R31") (pin "1") (pinfunction "1_1") (pintype "passive"))
      (node (ref "U11") (pin "5") (pinfunction "IN_5") (pintype "input"))
      (node (ref "U12") (pin "5") (pinfunction "IN_5") (pintype "input"))
      (node (ref "U2") (pin "8") (pinfunction "VO_8") (pintype "output"))
      (node (ref "U4") (pin "10") (pinfunction "VS_10") (pintype "passive"))
      (node (ref "U4") (pin "11") (pinfunction "ENABLE_2_11") (pintype "passive"))
      (node (ref "U5") (pin "10") (pinfunction "VS_10") (pintype "passive"))
      (node (ref "U5") (pin "11") (pinfunction "ENABLE_2_11") (pintype "passive"))
    )
    (net (code "135") (name "DOVDD-CSI") (class "Default")
      (node (ref "C4") (pin "1") (pinfunction "1_1") (pintype "passive"))
      (node (ref "C5") (pin "1") (pinfunction "1_1") (pintype "passive"))
      (node (ref "C6") (pin "1") (pinfunction "1_1") (pintype "passive"))
      (node (ref "J3") (pin "10") (pinfunction "10_10") (pintype "passive"))
      (node (ref "R6") (pin "2") (pinfunction "2_2") (pintype "passive"))
      (node (ref "R7") (pin "1") (pinfunction "1_1") (pintype "passive"))
      (node (ref "U1") (pin "2") (pinfunction "DOVDD-CSI_2") (pintype "passive"))
    )
    (net (code "136") (name "DVDD1V8-CSI") (class "Default")
      (node (ref "C2") (pin "1") (pinfunction "1_1") (pintype "passive"))
      (node (ref "J3") (pin "9") (pinfunction "9_9") (pintype "passive"))
      (node (ref "U1") (pin "13") (pinfunction "DVDD1V8-CSI_13") (pintype "passive"))
    )
    (net (code "137") (name "GND") (class "Default")
      (node (ref "ANT1") (pin "2") (pinfunction "2_2") (pintype "passive"))
      (node (ref "ANT1") (pin "3") (pinfunction "3_3") (pintype "passive"))
      (node (ref "C1") (pin "2") (pinfunction "2_2") (pintype "passive"))
      (node (ref "C10") (pin "1") (pinfunction "1_1") (pintype "passive"))
      (node (ref "C11") (pin "2") (pinfunction "2_2") (pintype "passive"))
      (node (ref "C12") (pin "2") (pinfunction "2_2") (pintype "passive"))
      (node (ref "C13") (pin "1") (pinfunction "1_1") (pintype "passive"))
      (node (ref "C14") (pin "2") (pinfunction "2_2") (pintype "passive"))
      (node (ref "C15") (pin "2") (pinfunction "2_2") (pintype "passive"))
      (node (ref "C16") (pin "2") (pinfunction "2_2") (pintype "passive"))
      (node (ref "C17") (pin "1") (pinfunction "1_1") (pintype "passive"))
      (node (ref "C18") (pin "1") (pinfunction "1_1") (pintype "passive"))
      (node (ref "C19") (pin "1") (pinfunction "1_1") (pintype "passive"))
      (node (ref "C2") (pin "2") (pinfunction "2_2") (pintype "passive"))
      (node (ref "C20") (pin "2") (pinfunction "2_2") (pintype "passive"))
      (node (ref "C21") (pin "2") (pinfunction "2_2") (pintype "passive"))
      (node (ref "C22") (pin "1") (pinfunction "1_1") (pintype "passive"))
      (node (ref "C26") (pin "2") (pinfunction "2_2") (pintype "passive"))
      (node (ref "C27") (pin "2") (pinfunction "2_2") (pintype "passive"))
      (node (ref "C29") (pin "2") (pinfunction "2_2") (pintype "passive"))
      (node (ref "C3") (pin "2") (pinfunction "2_2") (pintype "passive"))
      (node (ref "C31") (pin "2") (pinfunction "2_2") (pintype "passive"))
      (node (ref "C32") (pin "2") (pinfunction "2_2") (pintype "passive"))
      (node (ref "C33") (pin "2") (pinfunction "2_2") (pintype "passive"))
      (node (ref "C34") (pin "2") (pinfunction "2_2") (pintype "passive"))
      (node (ref "C35") (pin "2") (pinfunction "2_2") (pintype "passive"))
      (node (ref "C36") (pin "2") (pinfunction "2_2") (pintype "passive"))
      (node (ref "C37") (pin "2") (pinfunction "2_2") (pintype "passive"))
      (node (ref "C38") (pin "2") (pinfunction "2_2") (pintype "passive"))
      (node (ref "C39") (pin "2") (pinfunction "2_2") (pintype "passive"))
      (node (ref "C4") (pin "2") (pinfunction "2_2") (pintype "passive"))
      (node (ref "C40") (pin "1") (pinfunction "1_1") (pintype "passive"))
      (node (ref "C41") (pin "1") (pinfunction "1_1") (pintype "passive"))
      (node (ref "C42") (pin "1") (pinfunction "1_1") (pintype "passive"))
      (node (ref "C44") (pin "1") (pinfunction "1_1") (pintype "passive"))
      (node (ref "C45") (pin "2") (pinfunction "2_2") (pintype "passive"))
      (node (ref "C46") (pin "2") (pinfunction "2_2") (pintype "passive"))
      (node (ref "C47") (pin "1") (pinfunction "1_1") (pintype "passive"))
      (node (ref "C48") (pin "1") (pinfunction "1_1") (pintype "passive"))
      (node (ref "C49") (pin "1") (pinfunction "1_1") (pintype "passive"))
      (node (ref "C5") (pin "2") (pinfunction "2_2") (pintype "passive"))
      (node (ref "C50") (pin "2") (pinfunction "2_2") (pintype "passive"))
      (node (ref "C51") (pin "2") (pinfunction "2_2") (pintype "passive"))
      (node (ref "C52") (pin "1") (pinfunction "1_1") (pintype "passive"))
      (node (ref "C53") (pin "2") (pinfunction "2_2") (pintype "passive"))
      (node (ref "C54") (pin "2") (pinfunction "2_2") (pintype "passive"))
      (node (ref "C55") (pin "2") (pinfunction "2_2") (pintype "passive"))
      (node (ref "C56") (pin "2") (pinfunction "2_2") (pintype "passive"))
      (node (ref "C57") (pin "1") (pinfunction "1_1") (pintype "passive"))
      (node (ref "C6") (pin "2") (pinfunction "2_2") (pintype "passive"))
      (node (ref "C7") (pin "2") (pinfunction "2_2") (pintype "passive"))
      (node (ref "C8") (pin "1") (pinfunction "1_1") (pintype "passive"))
      (node (ref "C9") (pin "1") (pinfunction "1_1") (pintype "passive"))
      (node (ref "D13") (pin "1") (pinfunction "1_1") (pintype "passive"))
      (node (ref "D14") (pin "1") (pinfunction "1_1") (pintype "passive"))
      (node (ref "D15") (pin "1") (pinfunction "1_1") (pintype "passive"))
      (node (ref "D16") (pin "1") (pinfunction "1_1") (pintype "passive"))
      (node (ref "D19") (pin "2") (pinfunction "K_2") (pintype "passive"))
      (node (ref "D20") (pin "2") (pinfunction "K_2") (pintype "passive"))
      (node (ref "D21") (pin "1") (pinfunction "A_1") (pintype "passive"))
      (node (ref "D22") (pin "1") (pinfunction "A_1") (pintype "passive"))
      (node (ref "D23") (pin "1") (pinfunction "A_1") (pintype "passive"))
      (node (ref "D24") (pin "1") (pinfunction "A_1") (pintype "passive"))
      (node (ref "D5") (pin "1") (pinfunction "1_1") (pintype "passive"))
      (node (ref "D6") (pin "1") (pinfunction "1_1") (pintype "passive"))
      (node (ref "D7") (pin "1") (pinfunction "1_1") (pintype "passive"))
      (node (ref "D8") (pin "1") (pinfunction "1_1") (pintype "passive"))
      (node (ref "EC1") (pin "2") (pinfunction "2_2") (pintype "passive"))
      (node (ref "EC2") (pin "2") (pinfunction "2_2") (pintype "passive"))
      (node (ref "EC3") (pin "2") (pinfunction "2_2") (pintype "passive"))
      (node (ref "EC4") (pin "2") (pinfunction "2_2") (pintype "passive"))
      (node (ref "J1") (pin "1") (pinfunction "1_1") (pintype "passive"))
      (node (ref "J1") (pin "12") (pinfunction "12_12") (pintype "passive"))
      (node (ref "J1") (pin "13") (pinfunction "13_13") (pintype "passive"))
      (node (ref "J1") (pin "14") (pinfunction "14_14") (pintype "passive"))
      (node (ref "J1") (pin "9") (pinfunction "9_9") (pintype "passive"))
      (node (ref "J12") (pin "3") (pinfunction "3_3") (pintype "passive"))
      (node (ref "J12") (pin "4") (pinfunction "4_4") (pintype "passive"))
      (node (ref "J13") (pin "3") (pinfunction "3_3") (pintype "passive"))
      (node (ref "J13") (pin "4") (pinfunction "4_4") (pintype "passive"))
      (node (ref "J14") (pin "2") (pinfunction "2_2") (pintype "passive"))
      (node (ref "J15") (pin "4") (pinfunction "4_4") (pintype "passive"))
      (node (ref "J16") (pin "11") (pinfunction "GND_11") (pintype "passive"))
      (node (ref "J16") (pin "12") (pinfunction "GND_12") (pintype "passive"))
      (node (ref "J16") (pin "7") (pinfunction "VSS2_7") (pintype "passive"))
      (node (ref "J17") (pin "3") (pinfunction "3_3") (pintype "passive"))
      (node (ref "J19") (pin "4") (pinfunction "4_4") (pintype "passive"))
      (node (ref "J2") (pin "34") (pinfunction "34_34") (pintype "passive"))
      (node (ref "J2") (pin "41") (pinfunction "41_41") (pintype "passive"))
      (node (ref "J2") (pin "42") (pinfunction "42_42") (pintype "passive"))
      (node (ref "J2") (pin "5") (pinfunction "5_5") (pintype "passive"))
      (node (ref "J2") (pin "6") (pinfunction "6_6") (pintype "passive"))
      (node (ref "J2") (pin "9") (pinfunction "9_9") (pintype "passive"))
      (node (ref "J20") (pin "2") (pinfunction "2_2") (pintype "passive"))
      (node (ref "J22") (pin "2") (pinfunction "2_2") (pintype "passive"))
      (node (ref "J3") (pin "1") (pinfunction "1_1") (pintype "passive"))
      (node (ref "J3") (pin "12") (pinfunction "12_12") (pintype "passive"))
      (node (ref "J3") (pin "13") (pinfunction "13_13") (pintype "passive"))
      (node (ref "J3") (pin "14") (pinfunction "14_14") (pintype "passive"))
      (node (ref "J30") (pin "3") (pinfunction "3_3") (pintype "passive"))
      (node (ref "J40") (pin "3") (pinfunction "3_3") (pintype "passive"))
      (node (ref "J50") (pin "2") (pinfunction "2_2") (pintype "passive"))
      (node (ref "L10") (pin "1") (pinfunction "1_1") (pintype "passive"))
      (node (ref "L11") (pin "1") (pinfunction "1_1") (pintype "passive"))
      (node (ref "L12") (pin "1") (pinfunction "1_1") (pintype "passive"))
      (node (ref "L13") (pin "1") (pinfunction "1_1") (pintype "passive"))
      (node (ref "L15") (pin "1") (pinfunction "1_1") (pintype "passive"))
      (node (ref "L17") (pin "1") (pinfunction "1_1") (pintype "passive"))
      (node (ref "L18") (pin "1") (pinfunction "1_1") (pintype "passive"))
      (node (ref "L4") (pin "1") (pinfunction "1_1") (pintype "passive"))
      (node (ref "L5") (pin "1") (pinfunction "1_1") (pintype "passive"))
      (node (ref "L6") (pin "1") (pinfunction "1_1") (pintype "passive"))
      (node (ref "L7") (pin "1") (pinfunction "1_1") (pintype "passive"))
      (node (ref "L8") (pin "1") (pinfunction "1_1") (pintype "passive"))
      (node (ref "L9") (pin "1") (pinfunction "1_1") (pintype "passive"))
      (node (ref "R10") (pin "2") (pinfunction "2_2") (pintype "passive"))
      (node (ref "R11") (pin "2") (pinfunction "2_2") (pintype "passive"))
      (node (ref "R18") (pin "2") (pinfunction "2_2") (pintype "passive"))
      (node (ref "R19") (pin "2") (pinfunction "2_2") (pintype "passive"))
      (node (ref "R2") (pin "1") (pinfunction "1_1") (pintype "passive"))
      (node (ref "R41") (pin "2") (pinfunction "2_2") (pintype "passive"))
      (node (ref "R42") (pin "2") (pinfunction "2_2") (pintype "passive"))
      (node (ref "R47") (pin "2") (pinfunction "2_2") (pintype "passive"))
      (node (ref "R5") (pin "1") (pinfunction "1_1") (pintype "passive"))
      (node (ref "R51") (pin "2") (pinfunction "2_2") (pintype "passive"))
      (node (ref "R54") (pin "2") (pinfunction "2_2") (pintype "passive"))
      (node (ref "R55") (pin "1") (pinfunction "1_1") (pintype "passive"))
      (node (ref "R56") (pin "2") (pinfunction "2_2") (pintype "passive"))
      (node (ref "R57") (pin "2") (pinfunction "2_2") (pintype "passive"))
      (node (ref "R61") (pin "2") (pinfunction "2_2") (pintype "passive"))
      (node (ref "R62") (pin "2") (pinfunction "2_2") (pintype "passive"))
      (node (ref "R65") (pin "2") (pinfunction "2_2") (pintype "passive"))
      (node (ref "R69") (pin "1") (pinfunction "1_1") (pintype "passive"))
      (node (ref "R70") (pin "1") (pinfunction "1_1") (pintype "passive"))
      (node (ref "R73") (pin "2") (pinfunction "2_2") (pintype "passive"))
      (node (ref "R81") (pin "1") (pinfunction "1_1") (pintype "passive"))
      (node (ref "R82") (pin "1") (pinfunction "1_1") (pintype "passive"))
      (node (ref "SW1") (pin "2") (pinfunction "2_2") (pintype "passive"))
      (node (ref "SW2") (pin "2") (pinfunction "2_2") (pintype "passive"))
      (node (ref "SW3") (pin "2") (pinfunction "2_2") (pintype "passive"))
      (node (ref "SW4") (pin "2") (pinfunction "2_2") (pintype "passive"))
      (node (ref "U1") (pin "103") (pinfunction "GND_103") (pintype "passive"))
      (node (ref "U1") (pin "121") (pinfunction "GND_121") (pintype "passive"))
      (node (ref "U1") (pin "122") (pinfunction "GND_122") (pintype "passive"))
      (node (ref "U1") (pin "123") (pinfunction "GND_123") (pintype "passive"))
      (node (ref "U1") (pin "124") (pinfunction "GND_124") (pintype "passive"))
      (node (ref "U1") (pin "40") (pinfunction "GND_40") (pintype "passive"))
      (node (ref "U1") (pin "51") (pinfunction "GND_51") (pintype "passive"))
      (node (ref "U1") (pin "9") (pinfunction "GND_9") (pintype "passive"))
      (node (ref "U10") (pin "18") (pinfunction "GND/VSS_18") (pintype "passive"))
      (node (ref "U11") (pin "2") (pinfunction "GND_2") (pintype "power_in"))
      (node (ref "U12") (pin "2") (pinfunction "GND_2") (pintype "power_in"))
      (node (ref "U2") (pin "5") (pinfunction "GND_5") (pintype "power_in"))
      (node (ref "U3") (pin "1") (pinfunction "GND_1") (pintype "passive"))
      (node (ref "U4") (pin "14") (pinfunction "GND_14") (pintype "passive"))
      (node (ref "U4") (pin "15") (pinfunction "GND_15") (pintype "passive"))
      (node (ref "U4") (pin "16") (pinfunction "GND_16") (pintype "passive"))
      (node (ref "U4") (pin "17") (pinfunction "GND_17") (pintype "passive"))
      (node (ref "U4") (pin "4") (pinfunction "GND_4") (pintype "passive"))
      (node (ref "U4") (pin "5") (pinfunction "GND_5") (pintype "passive"))
      (node (ref "U4") (pin "6") (pinfunction "GND_6") (pintype "passive"))
      (node (ref "U4") (pin "7") (pinfunction "GND_7") (pintype "passive"))
      (node (ref "U5") (pin "14") (pinfunction "GND_14") (pintype "passive"))
      (node (ref "U5") (pin "15") (pinfunction "GND_15") (pintype "passive"))
      (node (ref "U5") (pin "16") (pinfunction "GND_16") (pintype "passive"))
      (node (ref "U5") (pin "17") (pinfunction "GND_17") (pintype "passive"))
      (node (ref "U5") (pin "4") (pinfunction "GND_4") (pintype "passive"))
      (node (ref "U5") (pin "5") (pinfunction "GND_5") (pintype "passive"))
      (node (ref "U5") (pin "6") (pinfunction "GND_6") (pintype "passive"))
      (node (ref "U5") (pin "7") (pinfunction "GND_7") (pintype "passive"))
      (node (ref "U6") (pin "1") (pinfunction "GND_1") (pintype "passive"))
      (node (ref "U7") (pin "2") (pinfunction "GND_2") (pintype "passive"))
      (node (ref "U9") (pin "1") (pinfunction "GND_1") (pintype "passive"))
      (node (ref "U9") (pin "20") (pinfunction "GND_20") (pintype "passive"))
      (node (ref "U9") (pin "3") (pinfunction "GND_3") (pintype "passive"))
      (node (ref "U9") (pin "31") (pinfunction "GND_31") (pintype "passive"))
      (node (ref "U9") (pin "33") (pinfunction "GND_33") (pintype "passive"))
      (node (ref "U9") (pin "36") (pinfunction "GND_36") (pintype "passive"))
      (node (ref "Y1") (pin "2") (pinfunction "GND_2") (pintype "passive"))
      (node (ref "Y1") (pin "4") (pinfunction "GND_4") (pintype "passive"))
    )
    (net (code "138") (name "HOST2_5V") (class "Default")
      (node (ref "C40") (pin "2") (pinfunction "2_2") (pintype "passive"))
      (node (ref "C45") (pin "1") (pinfunction "1_1") (pintype "passive"))
      (node (ref "C50") (pin "1") (pinfunction "1_1") (pintype "passive"))
      (node (ref "C51") (pin "1") (pinfunction "1_1") (pintype "passive"))
      (node (ref "C52") (pin "2") (pinfunction "2_2") (pintype "passive"))
      (node (ref "C53") (pin "1") (pinfunction "1_1") (pintype "passive"))
      (node (ref "J15") (pin "1") (pinfunction "1_1") (pintype "passive"))
      (node (ref "J18") (pin "1") (pinfunction "1_1") (pintype "passive"))
      (node (ref "L2") (pin "2") (pinfunction "2_2") (pintype "passive"))
      (node (ref "U1") (pin "12") (pinfunction "USBVBUS_12") (pintype "passive"))
      (node (ref "U11") (pin "1") (pinfunction "VOUT1_1") (pintype "output"))
      (node (ref "U12") (pin "1") (pinfunction "VOUT1_1") (pintype "output"))
    )
    (net (code "139") (name "Net-(ANT1-W)") (class "Default")
      (node (ref "ANT1") (pin "1") (pinfunction "W_1") (pintype "passive"))
      (node (ref "C41") (pin "2") (pinfunction "2_2") (pintype "passive"))
      (node (ref "C43") (pin "2") (pinfunction "2_2") (pintype "passive"))
    )
    (net (code "140") (name "Net-(C1-Pad1)") (class "Default")
      (node (ref "C1") (pin "1") (pinfunction "1_1") (pintype "passive"))
      (node (ref "R1") (pin "1") (pinfunction "1_1") (pintype "passive"))
    )
    (net (code "141") (name "Net-(C23-Pad1)") (class "Default")
      (node (ref "C23") (pin "1") (pinfunction "1_1") (pintype "passive"))
      (node (ref "J13") (pin "1") (pinfunction "1_1") (pintype "passive"))
      (node (ref "L14") (pin "1") (pinfunction "1_1") (pintype "passive"))
    )
    (net (code "142") (name "Net-(C25-Pad2)") (class "Default")
      (node (ref "C25") (pin "2") (pinfunction "2_2") (pintype "passive"))
      (node (ref "R49") (pin "1") (pinfunction "1_1") (pintype "passive"))
    )
    (net (code "143") (name "Net-(C28-Pad2)") (class "Default")
      (node (ref "C28") (pin "2") (pinfunction "2_2") (pintype "passive"))
      (node (ref "R50") (pin "1") (pinfunction "1_1") (pintype "passive"))
    )
    (net (code "144") (name "Net-(C30-Pad1)") (class "Default")
      (node (ref "C30") (pin "1") (pinfunction "1_1") (pintype "passive"))
      (node (ref "J13") (pin "2") (pinfunction "2_2") (pintype "passive"))
      (node (ref "L16") (pin "1") (pinfunction "1_1") (pintype "passive"))
    )
    (net (code "145") (name "Net-(D1-Pad2)") (class "Default")
      (node (ref "D1") (pin "2") (pinfunction "2_2") (pintype "passive"))
      (node (ref "D9") (pin "2") (pinfunction "2_2") (pintype "passive"))
      (node (ref "EC1") (pin "1") (pinfunction "1_1") (pintype "passive"))
    )
    (net (code "146") (name "Net-(D10-Pad2)") (class "Default")
      (node (ref "D10") (pin "2") (pinfunction "2_2") (pintype "passive"))
      (node (ref "D2") (pin "2") (pinfunction "2_2") (pintype "passive"))
      (node (ref "EC2") (pin "1") (pinfunction "1_1") (pintype "passive"))
    )
    (net (code "147") (name "Net-(D11-Pad2)") (class "Default")
      (node (ref "D11") (pin "2") (pinfunction "2_2") (pintype "passive"))
      (node (ref "D3") (pin "2") (pinfunction "2_2") (pintype "passive"))
      (node (ref "EC3") (pin "1") (pinfunction "1_1") (pintype "passive"))
    )
    (net (code "148") (name "Net-(D12-Pad2)") (class "Default")
      (node (ref "D12") (pin "2") (pinfunction "2_2") (pintype "passive"))
      (node (ref "D4") (pin "2") (pinfunction "2_2") (pintype "passive"))
      (node (ref "EC4") (pin "1") (pinfunction "1_1") (pintype "passive"))
    )
    (net (code "149") (name "Net-(J4-Pad1)") (class "Default")
      (node (ref "J4") (pin "1") (pinfunction "1_1") (pintype "passive"))
      (node (ref "R13") (pin "1") (pinfunction "1_1") (pintype "passive"))
    )
    (net (code "150") (name "Net-(J4-Pad4)") (class "Default")
      (node (ref "J4") (pin "4") (pinfunction "4_4") (pintype "passive"))
      (node (ref "R10") (pin "1") (pinfunction "1_1") (pintype "passive"))
    )
    (net (code "151") (name "Net-(J5-Pad1)") (class "Default")
      (node (ref "J5") (pin "1") (pinfunction "1_1") (pintype "passive"))
      (node (ref "R14") (pin "1") (pinfunction "1_1") (pintype "passive"))
    )
    (net (code "152") (name "Net-(J5-Pad4)") (class "Default")
      (node (ref "J5") (pin "4") (pinfunction "4_4") (pintype "passive"))
      (node (ref "R11") (pin "1") (pinfunction "1_1") (pintype "passive"))
    )
    (net (code "153") (name "Net-(J8-Pad1)") (class "Default")
      (node (ref "J8") (pin "1") (pinfunction "1_1") (pintype "passive"))
      (node (ref "R23") (pin "1") (pinfunction "1_1") (pintype "passive"))
    )
    (net (code "154") (name "Net-(J8-Pad4)") (class "Default")
      (node (ref "J8") (pin "4") (pinfunction "4_4") (pintype "passive"))
      (node (ref "R18") (pin "1") (pinfunction "1_1") (pintype "passive"))
    )
    (net (code "155") (name "Net-(J9-Pad1)") (class "Default")
      (node (ref "J9") (pin "1") (pinfunction "1_1") (pintype "passive"))
      (node (ref "R24") (pin "1") (pinfunction "1_1") (pintype "passive"))
    )
    (net (code "156") (name "Net-(J9-Pad4)") (class "Default")
      (node (ref "J9") (pin "4") (pinfunction "4_4") (pintype "passive"))
      (node (ref "R19") (pin "1") (pinfunction "1_1") (pintype "passive"))
    )
    (net (code "157") (name "Net-(J16-Voice_Key)") (class "Default")
      (node (ref "J16") (pin "1") (pinfunction "Voice_Key_1") (pintype "passive"))
      (node (ref "J50") (pin "1") (pinfunction "1_1") (pintype "passive"))
      (node (ref "R63") (pin "2") (pinfunction "2_2") (pintype "passive"))
    )
    (net (code "158") (name "Net-(J17-Pad1)") (class "Default")
      (node (ref "J17") (pin "1") (pinfunction "1_1") (pintype "passive"))
      (node (ref "R72") (pin "1") (pinfunction "1_1") (pintype "passive"))
    )
    (net (code "159") (name "Net-(J17-Pad2)") (class "Default")
      (node (ref "J17") (pin "2") (pinfunction "2_2") (pintype "passive"))
      (node (ref "R71") (pin "1") (pinfunction "1_1") (pintype "passive"))
    )
    (net (code "160") (name "Net-(J18-Pad4)") (class "Default")
      (node (ref "J18") (pin "4") (pinfunction "4_4") (pintype "passive"))
      (node (ref "R83") (pin "2") (pinfunction "2_2") (pintype "passive"))
      (node (ref "R84") (pin "1") (pinfunction "1_1") (pintype "passive"))
    )
    (net (code "161") (name "Net-(J21-Pad1)") (class "Default")
      (node (ref "J21") (pin "1") (pinfunction "1_1") (pintype "passive"))
      (node (ref "R48") (pin "1") (pinfunction "1_1") (pintype "passive"))
    )
    (net (code "162") (name "Net-(J22-Pad1)") (class "Default")
      (node (ref "J22") (pin "1") (pinfunction "1_1") (pintype "passive"))
      (node (ref "R52") (pin "1") (pinfunction "1_1") (pintype "passive"))
    )
    (net (code "163") (name "Net-(L3-Pad2)") (class "Default")
      (node (ref "L3") (pin "2") (pinfunction "2_2") (pintype "passive"))
      (node (ref "R1") (pin "2") (pinfunction "2_2") (pintype "passive"))
      (node (ref "U2") (pin "1") (pinfunction "LX_1") (pintype "passive"))
      (node (ref "U2") (pin "2") (pinfunction "LX_2") (pintype "passive"))
    )
    (net (code "164") (name "Net-(U1-PA-SHDN{slash}PH9)") (class "Default")
      (node (ref "R25") (pin "2") (pinfunction "2_2") (pintype "passive"))
      (node (ref "U1") (pin "39") (pinfunction "PA-SHDN/PH9_39") (pintype "passive"))
    )
    (net (code "165") (name "Net-(U2-EN)") (class "Default")
      (node (ref "C11") (pin "1") (pinfunction "1_1") (pintype "passive"))
      (node (ref "R4") (pin "1") (pinfunction "1_1") (pintype "passive"))
      (node (ref "U2") (pin "4") (pinfunction "EN_4") (pintype "passive"))
    )
    (net (code "166") (name "Net-(U2-FB)") (class "Default")
      (node (ref "R3") (pin "1") (pinfunction "1_1") (pintype "passive"))
      (node (ref "R5") (pin "2") (pinfunction "2_2") (pintype "passive"))
      (node (ref "U2") (pin "6") (pinfunction "FB_6") (pintype "passive"))
    )
    (net (code "167") (name "Net-(U2-OC)") (class "Default")
      (node (ref "R2") (pin "2") (pinfunction "2_2") (pintype "passive"))
      (node (ref "U2") (pin "7") (pinfunction "OC_7") (pintype "passive"))
    )
    (net (code "168") (name "Net-(U3-D1)") (class "Default")
      (node (ref "R15") (pin "2") (pinfunction "2_2") (pintype "passive"))
      (node (ref "U3") (pin "18") (pinfunction "D1_18") (pintype "passive"))
    )
    (net (code "169") (name "Net-(U3-D2)") (class "Default")
      (node (ref "R16") (pin "2") (pinfunction "2_2") (pintype "passive"))
      (node (ref "U3") (pin "17") (pinfunction "D2_17") (pintype "passive"))
    )
    (net (code "170") (name "Net-(U3-D3)") (class "Default")
      (node (ref "R17") (pin "2") (pinfunction "2_2") (pintype "passive"))
      (node (ref "U3") (pin "16") (pinfunction "D3_16") (pintype "passive"))
    )
    (net (code "171") (name "Net-(U3-D4)") (class "Default")
      (node (ref "R20") (pin "2") (pinfunction "2_2") (pintype "passive"))
      (node (ref "U3") (pin "15") (pinfunction "D4_15") (pintype "passive"))
    )
    (net (code "172") (name "Net-(U3-D5)") (class "Default")
      (node (ref "R21") (pin "2") (pinfunction "2_2") (pintype "passive"))
      (node (ref "U3") (pin "14") (pinfunction "D5_14") (pintype "passive"))
    )
    (net (code "173") (name "Net-(U3-D6)") (class "Default")
      (node (ref "R22") (pin "2") (pinfunction "2_2") (pintype "passive"))
      (node (ref "U3") (pin "13") (pinfunction "D6_13") (pintype "passive"))
    )
    (net (code "174") (name "Net-(U3-D7)") (class "Default")
      (node (ref "R26") (pin "2") (pinfunction "2_2") (pintype "passive"))
      (node (ref "U3") (pin "12") (pinfunction "D7_12") (pintype "passive"))
    )
    (net (code "175") (name "Net-(U3-D8)") (class "Default")
      (node (ref "R27") (pin "2") (pinfunction "2_2") (pintype "passive"))
      (node (ref "U3") (pin "11") (pinfunction "D8_11") (pintype "passive"))
    )
    (net (code "176") (name "Net-(U3-DREF)") (class "Default")
      (node (ref "C12") (pin "1") (pinfunction "1_1") (pintype "passive"))
      (node (ref "R12") (pin "1") (pinfunction "1_1") (pintype "passive"))
      (node (ref "U3") (pin "19") (pinfunction "DREF_19") (pintype "passive"))
      (node (ref "U3") (pin "20") (pinfunction "GREF_20") (pintype "passive"))
    )
    (net (code "177") (name "Net-(U3-SREF)") (class "Default")
      (node (ref "C13") (pin "2") (pinfunction "2_2") (pintype "passive"))
      (node (ref "U3") (pin "2") (pinfunction "SREF_2") (pintype "passive"))
    )
    (net (code "178") (name "Net-(U4-ENABLE_1)") (class "Default")
      (node (ref "R28") (pin "1") (pinfunction "1_1") (pintype "passive"))
      (node (ref "U4") (pin "1") (pinfunction "ENABLE_1_1") (pintype "passive"))
    )
    (net (code "179") (name "Net-(U4-VSS)") (class "Default")
      (node (ref "R29") (pin "2") (pinfunction "2_2") (pintype "passive"))
      (node (ref "U4") (pin "20") (pinfunction "VSS_20") (pintype "passive"))
    )
    (net (code "180") (name "Net-(U5-ENABLE_1)") (class "Default")
      (node (ref "R30") (pin "1") (pinfunction "1_1") (pintype "passive"))
      (node (ref "U5") (pin "1") (pinfunction "ENABLE_1_1") (pintype "passive"))
    )
    (net (code "181") (name "Net-(U5-VSS)") (class "Default")
      (node (ref "R31") (pin "2") (pinfunction "2_2") (pintype "passive"))
      (node (ref "U5") (pin "20") (pinfunction "VSS_20") (pintype "passive"))
    )
    (net (code "182") (name "Net-(U6-D1)") (class "Default")
      (node (ref "R33") (pin "2") (pinfunction "2_2") (pintype "passive"))
      (node (ref "U6") (pin "18") (pinfunction "D1_18") (pintype "passive"))
    )
    (net (code "183") (name "Net-(U6-D2)") (class "Default")
      (node (ref "R34") (pin "2") (pinfunction "2_2") (pintype "passive"))
      (node (ref "U6") (pin "17") (pinfunction "D2_17") (pintype "passive"))
    )
    (net (code "184") (name "Net-(U6-D3)") (class "Default")
      (node (ref "R35") (pin "2") (pinfunction "2_2") (pintype "passive"))
      (node (ref "U6") (pin "16") (pinfunction "D3_16") (pintype "passive"))
    )
    (net (code "185") (name "Net-(U6-D4)") (class "Default")
      (node (ref "R36") (pin "2") (pinfunction "2_2") (pintype "passive"))
      (node (ref "U6") (pin "15") (pinfunction "D4_15") (pintype "passive"))
    )
    (net (code "186") (name "Net-(U6-D5)") (class "Default")
      (node (ref "R37") (pin "2") (pinfunction "2_2") (pintype "passive"))
      (node (ref "U6") (pin "14") (pinfunction "D5_14") (pintype "passive"))
    )
    (net (code "187") (name "Net-(U6-D6)") (class "Default")
      (node (ref "R38") (pin "2") (pinfunction "2_2") (pintype "passive"))
      (node (ref "U6") (pin "13") (pinfunction "D6_13") (pintype "passive"))
    )
    (net (code "188") (name "Net-(U6-D7)") (class "Default")
      (node (ref "R39") (pin "2") (pinfunction "2_2") (pintype "passive"))
      (node (ref "U6") (pin "12") (pinfunction "D7_12") (pintype "passive"))
    )
    (net (code "189") (name "Net-(U6-D8)") (class "Default")
      (node (ref "R40") (pin "2") (pinfunction "2_2") (pintype "passive"))
      (node (ref "U6") (pin "11") (pinfunction "D8_11") (pintype "passive"))
    )
    (net (code "190") (name "Net-(U6-DREF)") (class "Default")
      (node (ref "C14") (pin "1") (pinfunction "1_1") (pintype "passive"))
      (node (ref "R32") (pin "1") (pinfunction "1_1") (pintype "passive"))
      (node (ref "U6") (pin "19") (pinfunction "DREF_19") (pintype "passive"))
      (node (ref "U6") (pin "20") (pinfunction "GREF_20") (pintype "passive"))
    )
    (net (code "191") (name "Net-(U6-SREF)") (class "Default")
      (node (ref "C17") (pin "2") (pinfunction "2_2") (pintype "passive"))
      (node (ref "U6") (pin "2") (pinfunction "SREF_2") (pintype "passive"))
    )
    (net (code "192") (name "Net-(U7-IN_A1)") (class "Default")
      (node (ref "R43") (pin "1") (pinfunction "1_1") (pintype "passive"))
      (node (ref "R46") (pin "2") (pinfunction "2_2") (pintype "passive"))
      (node (ref "U7") (pin "1") (pinfunction "IN_A1_1") (pintype "passive"))
      (node (ref "U7") (pin "4") (pinfunction "OUT_Y2_4") (pintype "passive"))
    )
    (net (code "193") (name "Net-(U7-IN_A2)") (class "Default")
      (node (ref "C31") (pin "1") (pinfunction "1_1") (pintype "passive"))
      (node (ref "R46") (pin "1") (pinfunction "1_1") (pintype "passive"))
      (node (ref "U7") (pin "3") (pinfunction "IN_A2_3") (pintype "passive"))
      (node (ref "Y1") (pin "3") (pinfunction "XO_3") (pintype "passive"))
    )
    (net (code "194") (name "Net-(U7-OUT_Y1)") (class "Default")
      (node (ref "R44") (pin "2") (pinfunction "2_2") (pintype "passive"))
      (node (ref "U7") (pin "6") (pinfunction "OUT_Y1_6") (pintype "passive"))
    )
    (net (code "195") (name "Net-(U7-VCC)") (class "Default")
      (node (ref "R45") (pin "2") (pinfunction "2_2") (pintype "passive"))
      (node (ref "U7") (pin "5") (pinfunction "VCC_5") (pintype "passive"))
    )
    (net (code "196") (name "Net-(U8-IN+)") (class "Default")
      (node (ref "R49") (pin "2") (pinfunction "2_2") (pintype "passive"))
      (node (ref "U8") (pin "3") (pinfunction "IN+_3") (pintype "passive"))
    )
    (net (code "197") (name "Net-(U8-IN-)") (class "Default")
      (node (ref "R50") (pin "2") (pinfunction "2_2") (pintype "passive"))
      (node (ref "U8") (pin "4") (pinfunction "IN-_4") (pintype "passive"))
    )
    (net (code "198") (name "Net-(U8-OUT+)") (class "Default")
      (node (ref "L14") (pin "2") (pinfunction "2_2") (pintype "passive"))
      (node (ref "U8") (pin "7") (pinfunction "OUT+_7") (pintype "passive"))
    )
    (net (code "199") (name "Net-(U8-OUT-)") (class "Default")
      (node (ref "L16") (pin "2") (pinfunction "2_2") (pintype "passive"))
      (node (ref "U8") (pin "6") (pinfunction "OUT-_6") (pintype "passive"))
    )
    (net (code "200") (name "Net-(U9-LPO)") (class "Default")
      (node (ref "R66") (pin "1") (pinfunction "1_1") (pintype "passive"))
      (node (ref "U9") (pin "24") (pinfunction "LPO_24") (pintype "passive"))
    )
    (net (code "201") (name "Net-(U9-SDIO_DATA_CLK)") (class "Default")
      (node (ref "R74") (pin "1") (pinfunction "1_1") (pintype "passive"))
      (node (ref "U9") (pin "17") (pinfunction "SDIO_DATA_CLK_17") (pintype "passive"))
    )
    (net (code "202") (name "Net-(U9-VIN_LDO)") (class "Default")
      (node (ref "C48") (pin "2") (pinfunction "2_2") (pintype "passive"))
      (node (ref "L19") (pin "2") (pinfunction "2_2") (pintype "passive"))
      (node (ref "U9") (pin "23") (pinfunction "VIN_LDO_23") (pintype "passive"))
    )
    (net (code "203") (name "Net-(U9-VIN_LDO_OUT)") (class "Default")
      (node (ref "L19") (pin "1") (pinfunction "1_1") (pintype "passive"))
      (node (ref "U9") (pin "21") (pinfunction "VIN_LDO_OUT_21") (pintype "passive"))
    )
    (net (code "204") (name "Net-(U9-WL_BT_ANT)") (class "Default")
      (node (ref "C42") (pin "2") (pinfunction "2_2") (pintype "passive"))
      (node (ref "C43") (pin "1") (pinfunction "1_1") (pintype "passive"))
      (node (ref "U9") (pin "2") (pinfunction "WL_BT_ANT_2") (pintype "passive"))
    )
    (net (code "205") (name "Net-(U9-WL_VDD_TCXO)") (class "Default")
      (node (ref "R64") (pin "1") (pinfunction "1_1") (pintype "passive"))
      (node (ref "U9") (pin "29") (pinfunction "WL_VDD_TCXO_29") (pintype "passive"))
    )
    (net (code "206") (name "Net-(U10-P3.0{slash}RXD)") (class "Default")
      (node (ref "R71") (pin "2") (pinfunction "2_2") (pintype "passive"))
      (node (ref "U10") (pin "4") (pinfunction "P3.0/RXD_4") (pintype "bidirectional"))
    )
    (net (code "207") (name "Net-(U10-P3.1{slash}TXD)") (class "Default")
      (node (ref "R72") (pin "2") (pinfunction "2_2") (pintype "passive"))
      (node (ref "U10") (pin "7") (pinfunction "P3.1/TXD_7") (pintype "bidirectional"))
    )
    (net (code "208") (name "Net-(U11-EN)") (class "Default")
      (node (ref "R67") (pin "2") (pinfunction "2_2") (pintype "passive"))
      (node (ref "R69") (pin "2") (pinfunction "2_2") (pintype "passive"))
      (node (ref "U11") (pin "4") (pinfunction "EN_4") (pintype "passive"))
    )
    (net (code "209") (name "Net-(U11-FLAG)") (class "Default")
      (node (ref "R70") (pin "2") (pinfunction "2_2") (pintype "passive"))
      (node (ref "U11") (pin "3") (pinfunction "FLAG_3") (pintype "passive"))
    )
    (net (code "210") (name "Net-(U12-EN)") (class "Default")
      (node (ref "R80") (pin "2") (pinfunction "2_2") (pintype "passive"))
      (node (ref "R81") (pin "2") (pinfunction "2_2") (pintype "passive"))
      (node (ref "U12") (pin "4") (pinfunction "EN_4") (pintype "passive"))
    )
    (net (code "211") (name "Net-(U12-FLAG)") (class "Default")
      (node (ref "R82") (pin "2") (pinfunction "2_2") (pintype "passive"))
      (node (ref "U12") (pin "3") (pinfunction "FLAG_3") (pintype "passive"))
    )
    (net (code "212") (name "Net-(Y1-XI)") (class "Default")
      (node (ref "C20") (pin "1") (pinfunction "1_1") (pintype "passive"))
      (node (ref "R43") (pin "2") (pinfunction "2_2") (pintype "passive"))
      (node (ref "Y1") (pin "1") (pinfunction "XI_1") (pintype "passive"))
    )
    (net (code "213") (name "PS") (class "Default")
      (node (ref "J21") (pin "2") (pinfunction "2_2") (pintype "passive"))
      (node (ref "U1") (pin "10") (pinfunction "PS_10") (pintype "passive"))
      (node (ref "U1") (pin "11") (pinfunction "PS_11") (pintype "passive"))
    )
    (net (code "214") (name "VBAT") (class "Default")
      (node (ref "C10") (pin "2") (pinfunction "2_2") (pintype "passive"))
      (node (ref "C32") (pin "1") (pinfunction "1_1") (pintype "passive"))
      (node (ref "J14") (pin "1") (pinfunction "1_1") (pintype "passive"))
      (node (ref "L3") (pin "1") (pinfunction "1_1") (pintype "passive"))
      (node (ref "U1") (pin "19") (pinfunction "VBAT_19") (pintype "passive"))
      (node (ref "U1") (pin "20") (pinfunction "VBAT_20") (pintype "passive"))
      (node (ref "U2") (pin "3") (pinfunction "VIN_3") (pintype "input"))
    )
    (net (code "215") (name "VCC-3V0") (class "Default")
      (node (ref "C29") (pin "1") (pinfunction "1_1") (pintype "passive"))
      (node (ref "C34") (pin "1") (pinfunction "1_1") (pintype "passive"))
      (node (ref "C36") (pin "1") (pinfunction "1_1") (pintype "passive"))
      (node (ref "C38") (pin "1") (pinfunction "1_1") (pintype "passive"))
      (node (ref "C39") (pin "1") (pinfunction "1_1") (pintype "passive"))
      (node (ref "J16") (pin "5") (pinfunction "VDD_5") (pintype "passive"))
      (node (ref "R12") (pin "2") (pinfunction "2_2") (pintype "passive"))
      (node (ref "R13") (pin "2") (pinfunction "2_2") (pintype "passive"))
      (node (ref "R14") (pin "2") (pinfunction "2_2") (pintype "passive"))
      (node (ref "R23") (pin "2") (pinfunction "2_2") (pintype "passive"))
      (node (ref "R24") (pin "2") (pinfunction "2_2") (pintype "passive"))
      (node (ref "R25") (pin "1") (pinfunction "1_1") (pintype "passive"))
      (node (ref "R32") (pin "2") (pinfunction "2_2") (pintype "passive"))
      (node (ref "R4") (pin "2") (pinfunction "2_2") (pintype "passive"))
      (node (ref "R52") (pin "2") (pinfunction "2_2") (pintype "passive"))
      (node (ref "R58") (pin "1") (pinfunction "1_1") (pintype "passive"))
      (node (ref "R84") (pin "2") (pinfunction "2_2") (pintype "passive"))
      (node (ref "U1") (pin "1") (pinfunction "VCC-3V0_1") (pintype "passive"))
      (node (ref "U10") (pin "41") (pinfunction "VIN5/V5_41") (pintype "passive"))
      (node (ref "U10") (pin "42") (pinfunction "VDD33/VDD/VCC_42") (pintype "passive"))
      (node (ref "U8") (pin "1") (pinfunction "SD_1") (pintype "passive"))
      (node (ref "U8") (pin "2") (pinfunction "ABD_2") (pintype "passive"))
      (node (ref "U8") (pin "5") (pinfunction "VDD_5") (pintype "passive"))
    )
    (net (code "216") (name "VCC-CTP") (class "Default")
      (node (ref "J2") (pin "35") (pinfunction "35_35") (pintype "passive"))
      (node (ref "J2") (pin "36") (pinfunction "36_36") (pintype "passive"))
      (node (ref "R8") (pin "1") (pinfunction "1_1") (pintype "passive"))
      (node (ref "R9") (pin "1") (pinfunction "1_1") (pintype "passive"))
      (node (ref "U1") (pin "6") (pinfunction "VCC-CTP_6") (pintype "passive"))
    )
    (net (code "217") (name "VCC-LCD") (class "Default")
      (node (ref "J2") (pin "7") (pinfunction "7_7") (pintype "passive"))
      (node (ref "J2") (pin "8") (pinfunction "8_8") (pintype "passive"))
      (node (ref "R53") (pin "2") (pinfunction "2_2") (pintype "passive"))
      (node (ref "U1") (pin "4") (pinfunction "VCC-LCD_4") (pintype "passive"))
    )
    (net (code "218") (name "VCC-WIFI") (class "Default")
      (node (ref "C46") (pin "1") (pinfunction "1_1") (pintype "passive"))
      (node (ref "C47") (pin "2") (pinfunction "2_2") (pintype "passive"))
      (node (ref "C54") (pin "1") (pinfunction "1_1") (pintype "passive"))
      (node (ref "R45") (pin "1") (pinfunction "1_1") (pintype "passive"))
      (node (ref "R59") (pin "1") (pinfunction "1_1") (pintype "passive"))
      (node (ref "R60") (pin "1") (pinfunction "1_1") (pintype "passive"))
      (node (ref "R64") (pin "2") (pinfunction "2_2") (pintype "passive"))
      (node (ref "R68") (pin "1") (pinfunction "1_1") (pintype "passive"))
      (node (ref "R75") (pin "1") (pinfunction "1_1") (pintype "passive"))
      (node (ref "R76") (pin "1") (pinfunction "1_1") (pintype "passive"))
      (node (ref "R77") (pin "1") (pinfunction "1_1") (pintype "passive"))
      (node (ref "R78") (pin "1") (pinfunction "1_1") (pintype "passive"))
      (node (ref "R79") (pin "1") (pinfunction "1_1") (pintype "passive"))
      (node (ref "U1") (pin "3") (pinfunction "VCC-IO-WIFI_3") (pintype "passive"))
      (node (ref "U9") (pin "22") (pinfunction "VDDIO_22") (pintype "passive"))
      (node (ref "U9") (pin "9") (pinfunction "VBAT_9") (pintype "passive"))
    )
    (net (code "219") (name "unconnected-(J2-Pad10)") (class "Default")
      (node (ref "J2") (pin "10") (pinfunction "10_10") (pintype "passive"))
    )
    (net (code "220") (name "unconnected-(J2-Pad11)") (class "Default")
      (node (ref "J2") (pin "11") (pinfunction "11_11") (pintype "passive"))
    )
    (net (code "221") (name "unconnected-(J2-Pad12)") (class "Default")
      (node (ref "J2") (pin "12") (pinfunction "12_12") (pintype "passive"))
    )
    (net (code "222") (name "unconnected-(J2-Pad13)") (class "Default")
      (node (ref "J2") (pin "13") (pinfunction "13_13") (pintype "passive"))
    )
    (net (code "223") (name "unconnected-(J2-Pad14)") (class "Default")
      (node (ref "J2") (pin "14") (pinfunction "14_14") (pintype "passive"))
    )
    (net (code "224") (name "unconnected-(J2-Pad15)") (class "Default")
      (node (ref "J2") (pin "15") (pinfunction "15_15") (pintype "passive"))
    )
    (net (code "225") (name "unconnected-(J2-Pad16)") (class "Default")
      (node (ref "J2") (pin "16") (pinfunction "16_16") (pintype "passive"))
    )
    (net (code "226") (name "unconnected-(J2-Pad17)") (class "Default")
      (node (ref "J2") (pin "17") (pinfunction "17_17") (pintype "passive"))
    )
    (net (code "227") (name "unconnected-(J2-Pad18)") (class "Default")
      (node (ref "J2") (pin "18") (pinfunction "18_18") (pintype "passive"))
    )
    (net (code "228") (name "unconnected-(J2-Pad19)") (class "Default")
      (node (ref "J2") (pin "19") (pinfunction "19_19") (pintype "passive"))
    )
    (net (code "229") (name "unconnected-(J2-Pad20)") (class "Default")
      (node (ref "J2") (pin "20") (pinfunction "20_20") (pintype "passive"))
    )
    (net (code "230") (name "unconnected-(J2-Pad21)") (class "Default")
      (node (ref "J2") (pin "21") (pinfunction "21_21") (pintype "passive"))
    )
    (net (code "231") (name "unconnected-(U1-NC-Pad125)") (class "Default")
      (node (ref "U1") (pin "125") (pinfunction "NC_125") (pintype "passive"))
    )
    (net (code "232") (name "unconnected-(U1-NC-Pad126)") (class "Default")
      (node (ref "U1") (pin "126") (pinfunction "NC_126") (pintype "passive"))
    )
    (net (code "233") (name "unconnected-(U1-PE14_CSI-RST-R-Pad77)") (class "Default")
      (node (ref "U1") (pin "77") (pinfunction "PE14_CSI-RST-R_77") (pintype "passive"))
    )
    (net (code "234") (name "unconnected-(U1-PE15_CSI-STBY-R-Pad78)") (class "Default")
      (node (ref "U1") (pin "78") (pinfunction "PE15_CSI-STBY-R_78") (pintype "passive"))
    )
    (net (code "235") (name "unconnected-(U1-PL11-Pad104)") (class "Default")
      (node (ref "U1") (pin "104") (pinfunction "PL11_104") (pintype "passive"))
    )
    (net (code "236") (name "unconnected-(U1-RESET-N-Pad22)") (class "Default")
      (node (ref "U1") (pin "22") (pinfunction "RESET-N_22") (pintype "passive"))
    )
    (net (code "237") (name "unconnected-(U1-UART2-RTS{slash}PB2-Pad26)") (class "Default")
      (node (ref "U1") (pin "26") (pinfunction "UART2-RTS/PB2_26") (pintype "passive"))
    )
    (net (code "238") (name "unconnected-(U1-UART3-RX{slash}PH7-Pad27)") (class "Default")
      (node (ref "U1") (pin "27") (pinfunction "UART3-RX/PH7_27") (pintype "passive"))
    )
    (net (code "239") (name "unconnected-(U1-UART3-TX{slash}PH6-Pad28)") (class "Default")
      (node (ref "U1") (pin "28") (pinfunction "UART3-TX/PH6_28") (pintype "passive"))
    )
    (net (code "240") (name "unconnected-(U1-VBAT-EXT-Pad17)") (class "Default")
      (node (ref "U1") (pin "17") (pinfunction "VBAT-EXT_17") (pintype "passive"))
    )
    (net (code "241") (name "unconnected-(U1-VBAT-EXT-Pad18)") (class "Default")
      (node (ref "U1") (pin "18") (pinfunction "VBAT-EXT_18") (pintype "passive"))
    )
    (net (code "242") (name "unconnected-(U1-VCC-RTC-Pad7)") (class "Default")
      (node (ref "U1") (pin "7") (pinfunction "VCC-RTC_7") (pintype "passive"))
    )
    (net (code "243") (name "unconnected-(U9-BT_XTAL_IN-Pad37)") (class "Default")
      (node (ref "U9") (pin "37") (pinfunction "BT_XTAL_IN_37") (pintype "passive"))
    )
    (net (code "244") (name "unconnected-(U9-BT_XTAL_OUT-Pad38)") (class "Default")
      (node (ref "U9") (pin "38") (pinfunction "BT_XTAL_OUT_38") (pintype "passive"))
    )
    (net (code "245") (name "unconnected-(U9-NC-Pad4)") (class "Default")
      (node (ref "U9") (pin "4") (pinfunction "NC_4") (pintype "passive"))
    )
    (net (code "246") (name "unconnected-(U9-NC-Pad5)") (class "Default")
      (node (ref "U9") (pin "5") (pinfunction "NC_5") (pintype "passive"))
    )
    (net (code "247") (name "unconnected-(U9-NC-Pad8)") (class "Default")
      (node (ref "U9") (pin "8") (pinfunction "NC_8") (pintype "passive"))
    )
    (net (code "248") (name "unconnected-(U9-NC-Pad10)") (class "Default")
      (node (ref "U9") (pin "10") (pinfunction "NC_10") (pintype "passive"))
    )
    (net (code "249") (name "unconnected-(U9-NC-Pad11)") (class "Default")
      (node (ref "U9") (pin "11") (pinfunction "NC_11") (pintype "passive"))
    )
    (net (code "250") (name "unconnected-(U9-NC-Pad32)") (class "Default")
      (node (ref "U9") (pin "32") (pinfunction "NC_32") (pintype "passive"))
    )
    (net (code "251") (name "unconnected-(U9-NC-Pad35)") (class "Default")
      (node (ref "U9") (pin "35") (pinfunction "NC_35") (pintype "passive"))
    )
    (net (code "252") (name "unconnected-(U9-NC-Pad39)") (class "Default")
      (node (ref "U9") (pin "39") (pinfunction "NC_39") (pintype "passive"))
    )
    (net (code "253") (name "unconnected-(U9-NC-Pad40)") (class "Default")
      (node (ref "U9") (pin "40") (pinfunction "NC_40") (pintype "passive"))
    )
    (net (code "254") (name "unconnected-(U9-NC-Pad45)") (class "Default")
      (node (ref "U9") (pin "45") (pinfunction "NC_45") (pintype "passive"))
    )
    (net (code "255") (name "unconnected-(U9-NC-Pad46)") (class "Default")
      (node (ref "U9") (pin "46") (pinfunction "NC_46") (pintype "passive"))
    )
    (net (code "256") (name "unconnected-(U9-NC-Pad47)") (class "Default")
      (node (ref "U9") (pin "47") (pinfunction "NC_47") (pintype "passive"))
    )
    (net (code "257") (name "unconnected-(U9-PCM_CLK-Pad26)") (class "Default")
      (node (ref "U9") (pin "26") (pinfunction "PCM_CLK_26") (pintype "passive"))
    )
    (net (code "258") (name "unconnected-(U9-PCM_IN-Pad27)") (class "Default")
      (node (ref "U9") (pin "27") (pinfunction "PCM_IN_27") (pintype "passive"))
    )
    (net (code "259") (name "unconnected-(U9-PCM_OUT-Pad25)") (class "Default")
      (node (ref "U9") (pin "25") (pinfunction "PCM_OUT_25") (pintype "passive"))
    )
    (net (code "260") (name "unconnected-(U9-PCM_SYNC-Pad28)") (class "Default")
      (node (ref "U9") (pin "28") (pinfunction "PCM_SYNC_28") (pintype "passive"))
    )
    (net (code "261") (name "unconnected-(U10-P0.2{slash}AD2{slash}RXD_-Pad38)") (class "Default")
      (node (ref "U10") (pin "38") (pinfunction "P0.2/AD2/RXD__38") (pintype "bidirectional"))
    )
    (net (code "262") (name "unconnected-(U10-P0.3{slash}AD3{slash}TXD_-Pad37)") (class "Default")
      (node (ref "U10") (pin "37") (pinfunction "P0.3/AD3/TXD__37") (pintype "bidirectional"))
    )
    (net (code "263") (name "unconnected-(U10-P1.6{slash}AIN6{slash}MISO-Pad1)") (class "Default")
      (node (ref "U10") (pin "1") (pinfunction "P1.6/AIN6/MISO_1") (pintype "bidirectional"))
    )
    (net (code "264") (name "unconnected-(U10-P1.7{slash}AIN7{slash}SCK-Pad2)") (class "Default")
      (node (ref "U10") (pin "2") (pinfunction "P1.7/AIN7/SCK_2") (pintype "bidirectional"))
    )
    (net (code "265") (name "unconnected-(U10-P2.0{slash}A8-Pad21)") (class "Default")
      (node (ref "U10") (pin "21") (pinfunction "P2.0/A8_21") (pintype "bidirectional"))
    )
    (net (code "266") (name "unconnected-(U10-P2.1{slash}MOSI1{slash}A9-Pad22)") (class "Default")
      (node (ref "U10") (pin "22") (pinfunction "P2.1/MOSI1/A9_22") (pintype "bidirectional"))
    )
    (net (code "267") (name "unconnected-(U10-P2.2{slash}MISO1{slash}A10-Pad23)") (class "Default")
      (node (ref "U10") (pin "23") (pinfunction "P2.2/MISO1/A10_23") (pintype "bidirectional"))
    )
    (net (code "268") (name "unconnected-(U10-P2.3{slash}SCK1{slash}A11-Pad24)") (class "Default")
      (node (ref "U10") (pin "24") (pinfunction "P2.3/SCK1/A11_24") (pintype "bidirectional"))
    )
    (net (code "269") (name "unconnected-(U10-P2.4{slash}PWM1{slash}A12-Pad25)") (class "Default")
      (node (ref "U10") (pin "25") (pinfunction "P2.4/PWM1/A12_25") (pintype "bidirectional"))
    )
    (net (code "270") (name "unconnected-(U10-P2.5_{slash}TNOW{slash}PWM2{slash}A13__{slash}T2EX_{slash}CAP2_-Pad26)") (class "Default")
      (node (ref "U10") (pin "26") (pinfunction "P2.5_/TNOW/PWM2/A13__/T2EX_/CAP2__26") (pintype "bidirectional"))
    )
    (net (code "271") (name "unconnected-(U10-P2.6{slash}RXD1{slash}A14-Pad27)") (class "Default")
      (node (ref "U10") (pin "27") (pinfunction "P2.6/RXD1/A14_27") (pintype "bidirectional"))
    )
    (net (code "272") (name "unconnected-(U10-P2.7{slash}TXD1{slash}DA7{slash}A15-Pad28)") (class "Default")
      (node (ref "U10") (pin "28") (pinfunction "P2.7/TXD1/DA7/A15_28") (pintype "bidirectional"))
    )
    (net (code "273") (name "unconnected-(U10-P3.2{slash}LED0{slash}INT0-Pad8)") (class "Default")
      (node (ref "U10") (pin "8") (pinfunction "P3.2/LED0/INT0_8") (pintype "bidirectional"))
    )
    (net (code "274") (name "unconnected-(U10-P3.3{slash}LED1{slash}!A15{slash}INT1-Pad9)") (class "Default")
      (node (ref "U10") (pin "9") (pinfunction "P3.3/LED1/!A15/INT1_9") (pintype "bidirectional"))
    )
    (net (code "275") (name "unconnected-(U10-P3.4{slash}LEDC{slash}XCS0{slash}T0-Pad10)") (class "Default")
      (node (ref "U10") (pin "10") (pinfunction "P3.4/LEDC/XCS0/T0_10") (pintype "bidirectional"))
    )
    (net (code "276") (name "unconnected-(U10-P3.5{slash}DA6{slash}T1-Pad11)") (class "Default")
      (node (ref "U10") (pin "11") (pinfunction "P3.5/DA6/T1_11") (pintype "bidirectional"))
    )
    (net (code "277") (name "unconnected-(U10-P3.6{slash}WR-Pad12)") (class "Default")
      (node (ref "U10") (pin "12") (pinfunction "P3.6/WR_12") (pintype "input"))
    )
    (net (code "278") (name "unconnected-(U10-P3.7{slash}RD-Pad13)") (class "Default")
      (node (ref "U10") (pin "13") (pinfunction "P3.7/RD_13") (pintype "bidirectional"))
    )
    (net (code "279") (name "unconnected-(U10-P4.0{slash}LED2{slash}A0{slash}RXD1_-Pad20)") (class "Default")
      (node (ref "U10") (pin "20") (pinfunction "P4.0/LED2/A0/RXD1__20") (pintype "bidirectional"))
    )
    (net (code "280") (name "unconnected-(U10-P4.1{slash}A1-Pad19)") (class "Default")
      (node (ref "U10") (pin "19") (pinfunction "P4.1/A1_19") (pintype "bidirectional"))
    )
    (net (code "281") (name "unconnected-(U10-P4.2{slash}PWM3_{slash}CAP3_{slash}A2-Pad15)") (class "Default")
      (node (ref "U10") (pin "15") (pinfunction "P4.2/PWM3_/CAP3_/A2_15") (pintype "bidirectional"))
    )
    (net (code "282") (name "unconnected-(U10-P4.3{slash}PWM1_{slash}A3-Pad14)") (class "Default")
      (node (ref "U10") (pin "14") (pinfunction "P4.3/PWM1_/A3_14") (pintype "bidirectional"))
    )
    (net (code "283") (name "unconnected-(U10-P4.4{slash}LED3{slash}TNOW_{slash}TXD1_{slash}A4-Pad6)") (class "Default")
      (node (ref "U10") (pin "6") (pinfunction "P4.4/LED3/TNOW_/TXD1_/A4_6") (pintype "bidirectional"))
    )
    (net (code "284") (name "unconnected-(U10-P4.5_{slash}PWM2_{slash}A5-Pad5)") (class "Default")
      (node (ref "U10") (pin "5") (pinfunction "P4.5_/PWM2_/A5_5") (pintype "bidirectional"))
    )
    (net (code "285") (name "unconnected-(U10-P4.6{slash}XI{slash}SCS_-Pad16)") (class "Default")
      (node (ref "U10") (pin "16") (pinfunction "P4.6/XI/SCS__16") (pintype "bidirectional"))
    )
    (net (code "286") (name "unconnected-(U10-P4.7{slash}X0{slash}SCK_-Pad17)") (class "Default")
      (node (ref "U10") (pin "17") (pinfunction "P4.7/X0/SCK__17") (pintype "bidirectional"))
    )
    (net (code "287") (name "unconnected-(U10-P5.4{slash}HM__{slash}ALE{slash}XB-Pad30)") (class "Default")
      (node (ref "U10") (pin "30") (pinfunction "P5.4/HM__/ALE/XB_30") (pintype "bidirectional"))
    )
    (net (code "288") (name "unconnected-(U10-P5.5_{slash}HP__{slash}!A15{slash}XA-Pad29)") (class "Default")
      (node (ref "U10") (pin "29") (pinfunction "P5.5_/HP__/!A15/XA_29") (pintype "bidirectional"))
    )
    (net (code "289") (name "unconnected-(U10-P5.7{slash}RST-Pad3)") (class "Default")
      (node (ref "U10") (pin "3") (pinfunction "P5.7/RST_3") (pintype "bidirectional"))
    )
  )
)
